# Testpoints.net
KiCad netlist of a schematic drawn in Altium Designer
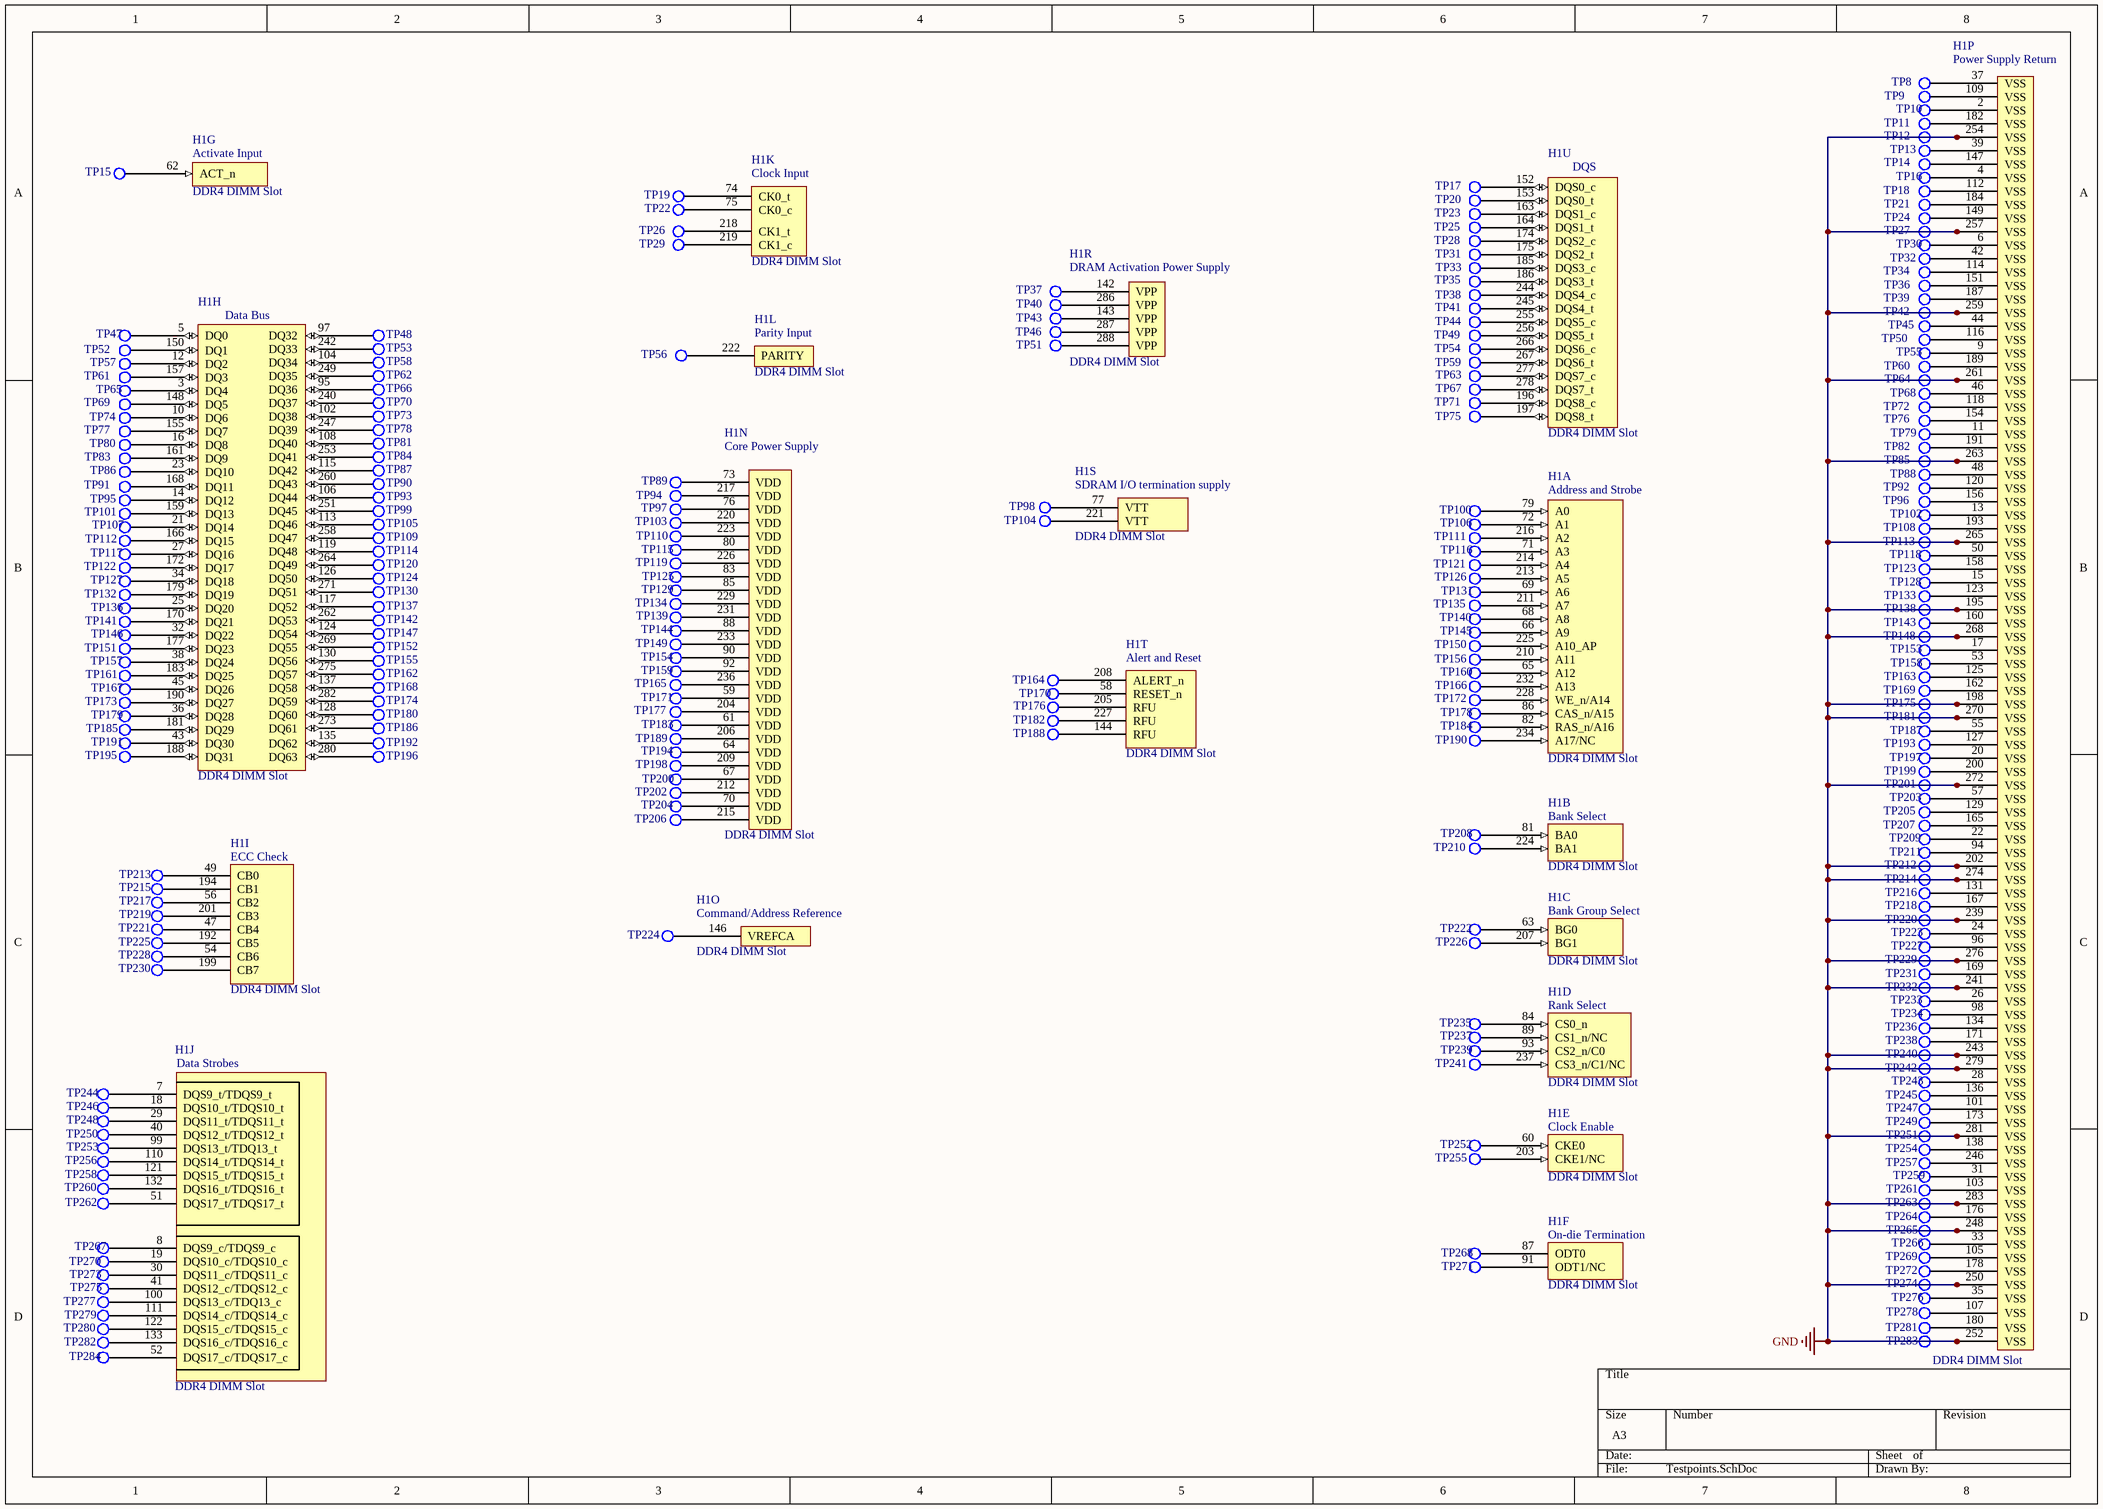
[diagram p0: Testpoints.SchDoc]

(export (version "E")
  (design (tool "Eeschema 10.0.6"))
  (components
    (comp (ref "H1")
      (value "DDR4 DIMM Slot")
      (footprint "DDR4 DIMM")
      (libsource (lib "RouterIntLib") (part "DDR4 DIMM Slot"))
    )
    (comp (ref "TP8")
      (value "Test Point")
      (footprint "Test Point")
      (libsource (lib "RouterIntLib") (part "Test Point"))
    )
    (comp (ref "TP9")
      (value "Test Point")
      (footprint "Test Point")
      (libsource (lib "RouterIntLib") (part "Test Point"))
    )
    (comp (ref "TP10")
      (value "Test Point")
      (footprint "Test Point")
      (libsource (lib "RouterIntLib") (part "Test Point"))
    )
    (comp (ref "TP11")
      (value "Test Point")
      (footprint "Test Point")
      (libsource (lib "RouterIntLib") (part "Test Point"))
    )
    (comp (ref "TP12")
      (value "Test Point")
      (footprint "Test Point")
      (libsource (lib "RouterIntLib") (part "Test Point"))
    )
    (comp (ref "TP13")
      (value "Test Point")
      (footprint "Test Point")
      (libsource (lib "RouterIntLib") (part "Test Point"))
    )
    (comp (ref "TP14")
      (value "Test Point")
      (footprint "Test Point")
      (libsource (lib "RouterIntLib") (part "Test Point"))
    )
    (comp (ref "TP15")
      (value "Test Point")
      (footprint "Test Point")
      (libsource (lib "RouterIntLib") (part "Test Point"))
    )
    (comp (ref "TP16")
      (value "Test Point")
      (footprint "Test Point")
      (libsource (lib "RouterIntLib") (part "Test Point"))
    )
    (comp (ref "TP17")
      (value "Test Point")
      (footprint "Test Point")
      (libsource (lib "RouterIntLib") (part "Test Point"))
    )
    (comp (ref "TP18")
      (value "Test Point")
      (footprint "Test Point")
      (libsource (lib "RouterIntLib") (part "Test Point"))
    )
    (comp (ref "TP19")
      (value "Test Point")
      (footprint "Test Point")
      (libsource (lib "RouterIntLib") (part "Test Point"))
    )
    (comp (ref "TP20")
      (value "Test Point")
      (footprint "Test Point")
      (libsource (lib "RouterIntLib") (part "Test Point"))
    )
    (comp (ref "TP21")
      (value "Test Point")
      (footprint "Test Point")
      (libsource (lib "RouterIntLib") (part "Test Point"))
    )
    (comp (ref "TP22")
      (value "Test Point")
      (footprint "Test Point")
      (libsource (lib "RouterIntLib") (part "Test Point"))
    )
    (comp (ref "TP23")
      (value "Test Point")
      (footprint "Test Point")
      (libsource (lib "RouterIntLib") (part "Test Point"))
    )
    (comp (ref "TP24")
      (value "Test Point")
      (footprint "Test Point")
      (libsource (lib "RouterIntLib") (part "Test Point"))
    )
    (comp (ref "TP25")
      (value "Test Point")
      (footprint "Test Point")
      (libsource (lib "RouterIntLib") (part "Test Point"))
    )
    (comp (ref "TP26")
      (value "Test Point")
      (footprint "Test Point")
      (libsource (lib "RouterIntLib") (part "Test Point"))
    )
    (comp (ref "TP27")
      (value "Test Point")
      (footprint "Test Point")
      (libsource (lib "RouterIntLib") (part "Test Point"))
    )
    (comp (ref "TP28")
      (value "Test Point")
      (footprint "Test Point")
      (libsource (lib "RouterIntLib") (part "Test Point"))
    )
    (comp (ref "TP29")
      (value "Test Point")
      (footprint "Test Point")
      (libsource (lib "RouterIntLib") (part "Test Point"))
    )
    (comp (ref "TP30")
      (value "Test Point")
      (footprint "Test Point")
      (libsource (lib "RouterIntLib") (part "Test Point"))
    )
    (comp (ref "TP31")
      (value "Test Point")
      (footprint "Test Point")
      (libsource (lib "RouterIntLib") (part "Test Point"))
    )
    (comp (ref "TP32")
      (value "Test Point")
      (footprint "Test Point")
      (libsource (lib "RouterIntLib") (part "Test Point"))
    )
    (comp (ref "TP33")
      (value "Test Point")
      (footprint "Test Point")
      (libsource (lib "RouterIntLib") (part "Test Point"))
    )
    (comp (ref "TP34")
      (value "Test Point")
      (footprint "Test Point")
      (libsource (lib "RouterIntLib") (part "Test Point"))
    )
    (comp (ref "TP35")
      (value "Test Point")
      (footprint "Test Point")
      (libsource (lib "RouterIntLib") (part "Test Point"))
    )
    (comp (ref "TP36")
      (value "Test Point")
      (footprint "Test Point")
      (libsource (lib "RouterIntLib") (part "Test Point"))
    )
    (comp (ref "TP37")
      (value "Test Point")
      (footprint "Test Point")
      (libsource (lib "RouterIntLib") (part "Test Point"))
    )
    (comp (ref "TP38")
      (value "Test Point")
      (footprint "Test Point")
      (libsource (lib "RouterIntLib") (part "Test Point"))
    )
    (comp (ref "TP39")
      (value "Test Point")
      (footprint "Test Point")
      (libsource (lib "RouterIntLib") (part "Test Point"))
    )
    (comp (ref "TP40")
      (value "Test Point")
      (footprint "Test Point")
      (libsource (lib "RouterIntLib") (part "Test Point"))
    )
    (comp (ref "TP41")
      (value "Test Point")
      (footprint "Test Point")
      (libsource (lib "RouterIntLib") (part "Test Point"))
    )
    (comp (ref "TP42")
      (value "Test Point")
      (footprint "Test Point")
      (libsource (lib "RouterIntLib") (part "Test Point"))
    )
    (comp (ref "TP43")
      (value "Test Point")
      (footprint "Test Point")
      (libsource (lib "RouterIntLib") (part "Test Point"))
    )
    (comp (ref "TP44")
      (value "Test Point")
      (footprint "Test Point")
      (libsource (lib "RouterIntLib") (part "Test Point"))
    )
    (comp (ref "TP45")
      (value "Test Point")
      (footprint "Test Point")
      (libsource (lib "RouterIntLib") (part "Test Point"))
    )
    (comp (ref "TP46")
      (value "Test Point")
      (footprint "Test Point")
      (libsource (lib "RouterIntLib") (part "Test Point"))
    )
    (comp (ref "TP47")
      (value "Test Point")
      (footprint "Test Point")
      (libsource (lib "RouterIntLib") (part "Test Point"))
    )
    (comp (ref "TP48")
      (value "Test Point")
      (footprint "Test Point")
      (libsource (lib "RouterIntLib") (part "Test Point"))
    )
    (comp (ref "TP49")
      (value "Test Point")
      (footprint "Test Point")
      (libsource (lib "RouterIntLib") (part "Test Point"))
    )
    (comp (ref "TP50")
      (value "Test Point")
      (footprint "Test Point")
      (libsource (lib "RouterIntLib") (part "Test Point"))
    )
    (comp (ref "TP51")
      (value "Test Point")
      (footprint "Test Point")
      (libsource (lib "RouterIntLib") (part "Test Point"))
    )
    (comp (ref "TP52")
      (value "Test Point")
      (footprint "Test Point")
      (libsource (lib "RouterIntLib") (part "Test Point"))
    )
    (comp (ref "TP53")
      (value "Test Point")
      (footprint "Test Point")
      (libsource (lib "RouterIntLib") (part "Test Point"))
    )
    (comp (ref "TP54")
      (value "Test Point")
      (footprint "Test Point")
      (libsource (lib "RouterIntLib") (part "Test Point"))
    )
    (comp (ref "TP55")
      (value "Test Point")
      (footprint "Test Point")
      (libsource (lib "RouterIntLib") (part "Test Point"))
    )
    (comp (ref "TP56")
      (value "Test Point")
      (footprint "Test Point")
      (libsource (lib "RouterIntLib") (part "Test Point"))
    )
    (comp (ref "TP57")
      (value "Test Point")
      (footprint "Test Point")
      (libsource (lib "RouterIntLib") (part "Test Point"))
    )
    (comp (ref "TP58")
      (value "Test Point")
      (footprint "Test Point")
      (libsource (lib "RouterIntLib") (part "Test Point"))
    )
    (comp (ref "TP59")
      (value "Test Point")
      (footprint "Test Point")
      (libsource (lib "RouterIntLib") (part "Test Point"))
    )
    (comp (ref "TP60")
      (value "Test Point")
      (footprint "Test Point")
      (libsource (lib "RouterIntLib") (part "Test Point"))
    )
    (comp (ref "TP61")
      (value "Test Point")
      (footprint "Test Point")
      (libsource (lib "RouterIntLib") (part "Test Point"))
    )
    (comp (ref "TP62")
      (value "Test Point")
      (footprint "Test Point")
      (libsource (lib "RouterIntLib") (part "Test Point"))
    )
    (comp (ref "TP63")
      (value "Test Point")
      (footprint "Test Point")
      (libsource (lib "RouterIntLib") (part "Test Point"))
    )
    (comp (ref "TP64")
      (value "Test Point")
      (footprint "Test Point")
      (libsource (lib "RouterIntLib") (part "Test Point"))
    )
    (comp (ref "TP65")
      (value "Test Point")
      (footprint "Test Point")
      (libsource (lib "RouterIntLib") (part "Test Point"))
    )
    (comp (ref "TP66")
      (value "Test Point")
      (footprint "Test Point")
      (libsource (lib "RouterIntLib") (part "Test Point"))
    )
    (comp (ref "TP67")
      (value "Test Point")
      (footprint "Test Point")
      (libsource (lib "RouterIntLib") (part "Test Point"))
    )
    (comp (ref "TP68")
      (value "Test Point")
      (footprint "Test Point")
      (libsource (lib "RouterIntLib") (part "Test Point"))
    )
    (comp (ref "TP69")
      (value "Test Point")
      (footprint "Test Point")
      (libsource (lib "RouterIntLib") (part "Test Point"))
    )
    (comp (ref "TP70")
      (value "Test Point")
      (footprint "Test Point")
      (libsource (lib "RouterIntLib") (part "Test Point"))
    )
    (comp (ref "TP71")
      (value "Test Point")
      (footprint "Test Point")
      (libsource (lib "RouterIntLib") (part "Test Point"))
    )
    (comp (ref "TP72")
      (value "Test Point")
      (footprint "Test Point")
      (libsource (lib "RouterIntLib") (part "Test Point"))
    )
    (comp (ref "TP73")
      (value "Test Point")
      (footprint "Test Point")
      (libsource (lib "RouterIntLib") (part "Test Point"))
    )
    (comp (ref "TP74")
      (value "Test Point")
      (footprint "Test Point")
      (libsource (lib "RouterIntLib") (part "Test Point"))
    )
    (comp (ref "TP75")
      (value "Test Point")
      (footprint "Test Point")
      (libsource (lib "RouterIntLib") (part "Test Point"))
    )
    (comp (ref "TP76")
      (value "Test Point")
      (footprint "Test Point")
      (libsource (lib "RouterIntLib") (part "Test Point"))
    )
    (comp (ref "TP77")
      (value "Test Point")
      (footprint "Test Point")
      (libsource (lib "RouterIntLib") (part "Test Point"))
    )
    (comp (ref "TP78")
      (value "Test Point")
      (footprint "Test Point")
      (libsource (lib "RouterIntLib") (part "Test Point"))
    )
    (comp (ref "TP79")
      (value "Test Point")
      (footprint "Test Point")
      (libsource (lib "RouterIntLib") (part "Test Point"))
    )
    (comp (ref "TP80")
      (value "Test Point")
      (footprint "Test Point")
      (libsource (lib "RouterIntLib") (part "Test Point"))
    )
    (comp (ref "TP81")
      (value "Test Point")
      (footprint "Test Point")
      (libsource (lib "RouterIntLib") (part "Test Point"))
    )
    (comp (ref "TP82")
      (value "Test Point")
      (footprint "Test Point")
      (libsource (lib "RouterIntLib") (part "Test Point"))
    )
    (comp (ref "TP83")
      (value "Test Point")
      (footprint "Test Point")
      (libsource (lib "RouterIntLib") (part "Test Point"))
    )
    (comp (ref "TP84")
      (value "Test Point")
      (footprint "Test Point")
      (libsource (lib "RouterIntLib") (part "Test Point"))
    )
    (comp (ref "TP85")
      (value "Test Point")
      (footprint "Test Point")
      (libsource (lib "RouterIntLib") (part "Test Point"))
    )
    (comp (ref "TP86")
      (value "Test Point")
      (footprint "Test Point")
      (libsource (lib "RouterIntLib") (part "Test Point"))
    )
    (comp (ref "TP87")
      (value "Test Point")
      (footprint "Test Point")
      (libsource (lib "RouterIntLib") (part "Test Point"))
    )
    (comp (ref "TP88")
      (value "Test Point")
      (footprint "Test Point")
      (libsource (lib "RouterIntLib") (part "Test Point"))
    )
    (comp (ref "TP89")
      (value "Test Point")
      (footprint "Test Point")
      (libsource (lib "RouterIntLib") (part "Test Point"))
    )
    (comp (ref "TP90")
      (value "Test Point")
      (footprint "Test Point")
      (libsource (lib "RouterIntLib") (part "Test Point"))
    )
    (comp (ref "TP91")
      (value "Test Point")
      (footprint "Test Point")
      (libsource (lib "RouterIntLib") (part "Test Point"))
    )
    (comp (ref "TP92")
      (value "Test Point")
      (footprint "Test Point")
      (libsource (lib "RouterIntLib") (part "Test Point"))
    )
    (comp (ref "TP93")
      (value "Test Point")
      (footprint "Test Point")
      (libsource (lib "RouterIntLib") (part "Test Point"))
    )
    (comp (ref "TP94")
      (value "Test Point")
      (footprint "Test Point")
      (libsource (lib "RouterIntLib") (part "Test Point"))
    )
    (comp (ref "TP95")
      (value "Test Point")
      (footprint "Test Point")
      (libsource (lib "RouterIntLib") (part "Test Point"))
    )
    (comp (ref "TP96")
      (value "Test Point")
      (footprint "Test Point")
      (libsource (lib "RouterIntLib") (part "Test Point"))
    )
    (comp (ref "TP97")
      (value "Test Point")
      (footprint "Test Point")
      (libsource (lib "RouterIntLib") (part "Test Point"))
    )
    (comp (ref "TP98")
      (value "Test Point")
      (footprint "Test Point")
      (libsource (lib "RouterIntLib") (part "Test Point"))
    )
    (comp (ref "TP99")
      (value "Test Point")
      (footprint "Test Point")
      (libsource (lib "RouterIntLib") (part "Test Point"))
    )
    (comp (ref "TP100")
      (value "Test Point")
      (footprint "Test Point")
      (libsource (lib "RouterIntLib") (part "Test Point"))
    )
    (comp (ref "TP101")
      (value "Test Point")
      (footprint "Test Point")
      (libsource (lib "RouterIntLib") (part "Test Point"))
    )
    (comp (ref "TP102")
      (value "Test Point")
      (footprint "Test Point")
      (libsource (lib "RouterIntLib") (part "Test Point"))
    )
    (comp (ref "TP103")
      (value "Test Point")
      (footprint "Test Point")
      (libsource (lib "RouterIntLib") (part "Test Point"))
    )
    (comp (ref "TP104")
      (value "Test Point")
      (footprint "Test Point")
      (libsource (lib "RouterIntLib") (part "Test Point"))
    )
    (comp (ref "TP105")
      (value "Test Point")
      (footprint "Test Point")
      (libsource (lib "RouterIntLib") (part "Test Point"))
    )
    (comp (ref "TP106")
      (value "Test Point")
      (footprint "Test Point")
      (libsource (lib "RouterIntLib") (part "Test Point"))
    )
    (comp (ref "TP107")
      (value "Test Point")
      (footprint "Test Point")
      (libsource (lib "RouterIntLib") (part "Test Point"))
    )
    (comp (ref "TP108")
      (value "Test Point")
      (footprint "Test Point")
      (libsource (lib "RouterIntLib") (part "Test Point"))
    )
    (comp (ref "TP109")
      (value "Test Point")
      (footprint "Test Point")
      (libsource (lib "RouterIntLib") (part "Test Point"))
    )
    (comp (ref "TP110")
      (value "Test Point")
      (footprint "Test Point")
      (libsource (lib "RouterIntLib") (part "Test Point"))
    )
    (comp (ref "TP111")
      (value "Test Point")
      (footprint "Test Point")
      (libsource (lib "RouterIntLib") (part "Test Point"))
    )
    (comp (ref "TP112")
      (value "Test Point")
      (footprint "Test Point")
      (libsource (lib "RouterIntLib") (part "Test Point"))
    )
    (comp (ref "TP113")
      (value "Test Point")
      (footprint "Test Point")
      (libsource (lib "RouterIntLib") (part "Test Point"))
    )
    (comp (ref "TP114")
      (value "Test Point")
      (footprint "Test Point")
      (libsource (lib "RouterIntLib") (part "Test Point"))
    )
    (comp (ref "TP115")
      (value "Test Point")
      (footprint "Test Point")
      (libsource (lib "RouterIntLib") (part "Test Point"))
    )
    (comp (ref "TP116")
      (value "Test Point")
      (footprint "Test Point")
      (libsource (lib "RouterIntLib") (part "Test Point"))
    )
    (comp (ref "TP117")
      (value "Test Point")
      (footprint "Test Point")
      (libsource (lib "RouterIntLib") (part "Test Point"))
    )
    (comp (ref "TP118")
      (value "Test Point")
      (footprint "Test Point")
      (libsource (lib "RouterIntLib") (part "Test Point"))
    )
    (comp (ref "TP119")
      (value "Test Point")
      (footprint "Test Point")
      (libsource (lib "RouterIntLib") (part "Test Point"))
    )
    (comp (ref "TP120")
      (value "Test Point")
      (footprint "Test Point")
      (libsource (lib "RouterIntLib") (part "Test Point"))
    )
    (comp (ref "TP121")
      (value "Test Point")
      (footprint "Test Point")
      (libsource (lib "RouterIntLib") (part "Test Point"))
    )
    (comp (ref "TP122")
      (value "Test Point")
      (footprint "Test Point")
      (libsource (lib "RouterIntLib") (part "Test Point"))
    )
    (comp (ref "TP123")
      (value "Test Point")
      (footprint "Test Point")
      (libsource (lib "RouterIntLib") (part "Test Point"))
    )
    (comp (ref "TP124")
      (value "Test Point")
      (footprint "Test Point")
      (libsource (lib "RouterIntLib") (part "Test Point"))
    )
    (comp (ref "TP125")
      (value "Test Point")
      (footprint "Test Point")
      (libsource (lib "RouterIntLib") (part "Test Point"))
    )
    (comp (ref "TP126")
      (value "Test Point")
      (footprint "Test Point")
      (libsource (lib "RouterIntLib") (part "Test Point"))
    )
    (comp (ref "TP127")
      (value "Test Point")
      (footprint "Test Point")
      (libsource (lib "RouterIntLib") (part "Test Point"))
    )
    (comp (ref "TP128")
      (value "Test Point")
      (footprint "Test Point")
      (libsource (lib "RouterIntLib") (part "Test Point"))
    )
    (comp (ref "TP129")
      (value "Test Point")
      (footprint "Test Point")
      (libsource (lib "RouterIntLib") (part "Test Point"))
    )
    (comp (ref "TP130")
      (value "Test Point")
      (footprint "Test Point")
      (libsource (lib "RouterIntLib") (part "Test Point"))
    )
    (comp (ref "TP131")
      (value "Test Point")
      (footprint "Test Point")
      (libsource (lib "RouterIntLib") (part "Test Point"))
    )
    (comp (ref "TP132")
      (value "Test Point")
      (footprint "Test Point")
      (libsource (lib "RouterIntLib") (part "Test Point"))
    )
    (comp (ref "TP133")
      (value "Test Point")
      (footprint "Test Point")
      (libsource (lib "RouterIntLib") (part "Test Point"))
    )
    (comp (ref "TP134")
      (value "Test Point")
      (footprint "Test Point")
      (libsource (lib "RouterIntLib") (part "Test Point"))
    )
    (comp (ref "TP135")
      (value "Test Point")
      (footprint "Test Point")
      (libsource (lib "RouterIntLib") (part "Test Point"))
    )
    (comp (ref "TP136")
      (value "Test Point")
      (footprint "Test Point")
      (libsource (lib "RouterIntLib") (part "Test Point"))
    )
    (comp (ref "TP137")
      (value "Test Point")
      (footprint "Test Point")
      (libsource (lib "RouterIntLib") (part "Test Point"))
    )
    (comp (ref "TP138")
      (value "Test Point")
      (footprint "Test Point")
      (libsource (lib "RouterIntLib") (part "Test Point"))
    )
    (comp (ref "TP139")
      (value "Test Point")
      (footprint "Test Point")
      (libsource (lib "RouterIntLib") (part "Test Point"))
    )
    (comp (ref "TP140")
      (value "Test Point")
      (footprint "Test Point")
      (libsource (lib "RouterIntLib") (part "Test Point"))
    )
    (comp (ref "TP141")
      (value "Test Point")
      (footprint "Test Point")
      (libsource (lib "RouterIntLib") (part "Test Point"))
    )
    (comp (ref "TP142")
      (value "Test Point")
      (footprint "Test Point")
      (libsource (lib "RouterIntLib") (part "Test Point"))
    )
    (comp (ref "TP143")
      (value "Test Point")
      (footprint "Test Point")
      (libsource (lib "RouterIntLib") (part "Test Point"))
    )
    (comp (ref "TP144")
      (value "Test Point")
      (footprint "Test Point")
      (libsource (lib "RouterIntLib") (part "Test Point"))
    )
    (comp (ref "TP145")
      (value "Test Point")
      (footprint "Test Point")
      (libsource (lib "RouterIntLib") (part "Test Point"))
    )
    (comp (ref "TP146")
      (value "Test Point")
      (footprint "Test Point")
      (libsource (lib "RouterIntLib") (part "Test Point"))
    )
    (comp (ref "TP147")
      (value "Test Point")
      (footprint "Test Point")
      (libsource (lib "RouterIntLib") (part "Test Point"))
    )
    (comp (ref "TP148")
      (value "Test Point")
      (footprint "Test Point")
      (libsource (lib "RouterIntLib") (part "Test Point"))
    )
    (comp (ref "TP149")
      (value "Test Point")
      (footprint "Test Point")
      (libsource (lib "RouterIntLib") (part "Test Point"))
    )
    (comp (ref "TP150")
      (value "Test Point")
      (footprint "Test Point")
      (libsource (lib "RouterIntLib") (part "Test Point"))
    )
    (comp (ref "TP151")
      (value "Test Point")
      (footprint "Test Point")
      (libsource (lib "RouterIntLib") (part "Test Point"))
    )
    (comp (ref "TP152")
      (value "Test Point")
      (footprint "Test Point")
      (libsource (lib "RouterIntLib") (part "Test Point"))
    )
    (comp (ref "TP153")
      (value "Test Point")
      (footprint "Test Point")
      (libsource (lib "RouterIntLib") (part "Test Point"))
    )
    (comp (ref "TP154")
      (value "Test Point")
      (footprint "Test Point")
      (libsource (lib "RouterIntLib") (part "Test Point"))
    )
    (comp (ref "TP155")
      (value "Test Point")
      (footprint "Test Point")
      (libsource (lib "RouterIntLib") (part "Test Point"))
    )
    (comp (ref "TP156")
      (value "Test Point")
      (footprint "Test Point")
      (libsource (lib "RouterIntLib") (part "Test Point"))
    )
    (comp (ref "TP157")
      (value "Test Point")
      (footprint "Test Point")
      (libsource (lib "RouterIntLib") (part "Test Point"))
    )
    (comp (ref "TP158")
      (value "Test Point")
      (footprint "Test Point")
      (libsource (lib "RouterIntLib") (part "Test Point"))
    )
    (comp (ref "TP159")
      (value "Test Point")
      (footprint "Test Point")
      (libsource (lib "RouterIntLib") (part "Test Point"))
    )
    (comp (ref "TP160")
      (value "Test Point")
      (footprint "Test Point")
      (libsource (lib "RouterIntLib") (part "Test Point"))
    )
    (comp (ref "TP161")
      (value "Test Point")
      (footprint "Test Point")
      (libsource (lib "RouterIntLib") (part "Test Point"))
    )
    (comp (ref "TP162")
      (value "Test Point")
      (footprint "Test Point")
      (libsource (lib "RouterIntLib") (part "Test Point"))
    )
    (comp (ref "TP163")
      (value "Test Point")
      (footprint "Test Point")
      (libsource (lib "RouterIntLib") (part "Test Point"))
    )
    (comp (ref "TP164")
      (value "Test Point")
      (footprint "Test Point")
      (libsource (lib "RouterIntLib") (part "Test Point"))
    )
    (comp (ref "TP165")
      (value "Test Point")
      (footprint "Test Point")
      (libsource (lib "RouterIntLib") (part "Test Point"))
    )
    (comp (ref "TP166")
      (value "Test Point")
      (footprint "Test Point")
      (libsource (lib "RouterIntLib") (part "Test Point"))
    )
    (comp (ref "TP167")
      (value "Test Point")
      (footprint "Test Point")
      (libsource (lib "RouterIntLib") (part "Test Point"))
    )
    (comp (ref "TP168")
      (value "Test Point")
      (footprint "Test Point")
      (libsource (lib "RouterIntLib") (part "Test Point"))
    )
    (comp (ref "TP169")
      (value "Test Point")
      (footprint "Test Point")
      (libsource (lib "RouterIntLib") (part "Test Point"))
    )
    (comp (ref "TP170")
      (value "Test Point")
      (footprint "Test Point")
      (libsource (lib "RouterIntLib") (part "Test Point"))
    )
    (comp (ref "TP171")
      (value "Test Point")
      (footprint "Test Point")
      (libsource (lib "RouterIntLib") (part "Test Point"))
    )
    (comp (ref "TP172")
      (value "Test Point")
      (footprint "Test Point")
      (libsource (lib "RouterIntLib") (part "Test Point"))
    )
    (comp (ref "TP173")
      (value "Test Point")
      (footprint "Test Point")
      (libsource (lib "RouterIntLib") (part "Test Point"))
    )
    (comp (ref "TP174")
      (value "Test Point")
      (footprint "Test Point")
      (libsource (lib "RouterIntLib") (part "Test Point"))
    )
    (comp (ref "TP175")
      (value "Test Point")
      (footprint "Test Point")
      (libsource (lib "RouterIntLib") (part "Test Point"))
    )
    (comp (ref "TP176")
      (value "Test Point")
      (footprint "Test Point")
      (libsource (lib "RouterIntLib") (part "Test Point"))
    )
    (comp (ref "TP177")
      (value "Test Point")
      (footprint "Test Point")
      (libsource (lib "RouterIntLib") (part "Test Point"))
    )
    (comp (ref "TP178")
      (value "Test Point")
      (footprint "Test Point")
      (libsource (lib "RouterIntLib") (part "Test Point"))
    )
    (comp (ref "TP179")
      (value "Test Point")
      (footprint "Test Point")
      (libsource (lib "RouterIntLib") (part "Test Point"))
    )
    (comp (ref "TP180")
      (value "Test Point")
      (footprint "Test Point")
      (libsource (lib "RouterIntLib") (part "Test Point"))
    )
    (comp (ref "TP181")
      (value "Test Point")
      (footprint "Test Point")
      (libsource (lib "RouterIntLib") (part "Test Point"))
    )
    (comp (ref "TP182")
      (value "Test Point")
      (footprint "Test Point")
      (libsource (lib "RouterIntLib") (part "Test Point"))
    )
    (comp (ref "TP183")
      (value "Test Point")
      (footprint "Test Point")
      (libsource (lib "RouterIntLib") (part "Test Point"))
    )
    (comp (ref "TP184")
      (value "Test Point")
      (footprint "Test Point")
      (libsource (lib "RouterIntLib") (part "Test Point"))
    )
    (comp (ref "TP185")
      (value "Test Point")
      (footprint "Test Point")
      (libsource (lib "RouterIntLib") (part "Test Point"))
    )
    (comp (ref "TP186")
      (value "Test Point")
      (footprint "Test Point")
      (libsource (lib "RouterIntLib") (part "Test Point"))
    )
    (comp (ref "TP187")
      (value "Test Point")
      (footprint "Test Point")
      (libsource (lib "RouterIntLib") (part "Test Point"))
    )
    (comp (ref "TP188")
      (value "Test Point")
      (footprint "Test Point")
      (libsource (lib "RouterIntLib") (part "Test Point"))
    )
    (comp (ref "TP189")
      (value "Test Point")
      (footprint "Test Point")
      (libsource (lib "RouterIntLib") (part "Test Point"))
    )
    (comp (ref "TP190")
      (value "Test Point")
      (footprint "Test Point")
      (libsource (lib "RouterIntLib") (part "Test Point"))
    )
    (comp (ref "TP191")
      (value "Test Point")
      (footprint "Test Point")
      (libsource (lib "RouterIntLib") (part "Test Point"))
    )
    (comp (ref "TP192")
      (value "Test Point")
      (footprint "Test Point")
      (libsource (lib "RouterIntLib") (part "Test Point"))
    )
    (comp (ref "TP193")
      (value "Test Point")
      (footprint "Test Point")
      (libsource (lib "RouterIntLib") (part "Test Point"))
    )
    (comp (ref "TP194")
      (value "Test Point")
      (footprint "Test Point")
      (libsource (lib "RouterIntLib") (part "Test Point"))
    )
    (comp (ref "TP195")
      (value "Test Point")
      (footprint "Test Point")
      (libsource (lib "RouterIntLib") (part "Test Point"))
    )
    (comp (ref "TP196")
      (value "Test Point")
      (footprint "Test Point")
      (libsource (lib "RouterIntLib") (part "Test Point"))
    )
    (comp (ref "TP197")
      (value "Test Point")
      (footprint "Test Point")
      (libsource (lib "RouterIntLib") (part "Test Point"))
    )
    (comp (ref "TP198")
      (value "Test Point")
      (footprint "Test Point")
      (libsource (lib "RouterIntLib") (part "Test Point"))
    )
    (comp (ref "TP199")
      (value "Test Point")
      (footprint "Test Point")
      (libsource (lib "RouterIntLib") (part "Test Point"))
    )
    (comp (ref "TP200")
      (value "Test Point")
      (footprint "Test Point")
      (libsource (lib "RouterIntLib") (part "Test Point"))
    )
    (comp (ref "TP201")
      (value "Test Point")
      (footprint "Test Point")
      (libsource (lib "RouterIntLib") (part "Test Point"))
    )
    (comp (ref "TP202")
      (value "Test Point")
      (footprint "Test Point")
      (libsource (lib "RouterIntLib") (part "Test Point"))
    )
    (comp (ref "TP203")
      (value "Test Point")
      (footprint "Test Point")
      (libsource (lib "RouterIntLib") (part "Test Point"))
    )
    (comp (ref "TP204")
      (value "Test Point")
      (footprint "Test Point")
      (libsource (lib "RouterIntLib") (part "Test Point"))
    )
    (comp (ref "TP205")
      (value "Test Point")
      (footprint "Test Point")
      (libsource (lib "RouterIntLib") (part "Test Point"))
    )
    (comp (ref "TP206")
      (value "Test Point")
      (footprint "Test Point")
      (libsource (lib "RouterIntLib") (part "Test Point"))
    )
    (comp (ref "TP207")
      (value "Test Point")
      (footprint "Test Point")
      (libsource (lib "RouterIntLib") (part "Test Point"))
    )
    (comp (ref "TP208")
      (value "Test Point")
      (footprint "Test Point")
      (libsource (lib "RouterIntLib") (part "Test Point"))
    )
    (comp (ref "TP209")
      (value "Test Point")
      (footprint "Test Point")
      (libsource (lib "RouterIntLib") (part "Test Point"))
    )
    (comp (ref "TP210")
      (value "Test Point")
      (footprint "Test Point")
      (libsource (lib "RouterIntLib") (part "Test Point"))
    )
    (comp (ref "TP211")
      (value "Test Point")
      (footprint "Test Point")
      (libsource (lib "RouterIntLib") (part "Test Point"))
    )
    (comp (ref "TP212")
      (value "Test Point")
      (footprint "Test Point")
      (libsource (lib "RouterIntLib") (part "Test Point"))
    )
    (comp (ref "TP213")
      (value "Test Point")
      (footprint "Test Point")
      (libsource (lib "RouterIntLib") (part "Test Point"))
    )
    (comp (ref "TP214")
      (value "Test Point")
      (footprint "Test Point")
      (libsource (lib "RouterIntLib") (part "Test Point"))
    )
    (comp (ref "TP215")
      (value "Test Point")
      (footprint "Test Point")
      (libsource (lib "RouterIntLib") (part "Test Point"))
    )
    (comp (ref "TP216")
      (value "Test Point")
      (footprint "Test Point")
      (libsource (lib "RouterIntLib") (part "Test Point"))
    )
    (comp (ref "TP217")
      (value "Test Point")
      (footprint "Test Point")
      (libsource (lib "RouterIntLib") (part "Test Point"))
    )
    (comp (ref "TP218")
      (value "Test Point")
      (footprint "Test Point")
      (libsource (lib "RouterIntLib") (part "Test Point"))
    )
    (comp (ref "TP219")
      (value "Test Point")
      (footprint "Test Point")
      (libsource (lib "RouterIntLib") (part "Test Point"))
    )
    (comp (ref "TP220")
      (value "Test Point")
      (footprint "Test Point")
      (libsource (lib "RouterIntLib") (part "Test Point"))
    )
    (comp (ref "TP221")
      (value "Test Point")
      (footprint "Test Point")
      (libsource (lib "RouterIntLib") (part "Test Point"))
    )
    (comp (ref "TP222")
      (value "Test Point")
      (footprint "Test Point")
      (libsource (lib "RouterIntLib") (part "Test Point"))
    )
    (comp (ref "TP223")
      (value "Test Point")
      (footprint "Test Point")
      (libsource (lib "RouterIntLib") (part "Test Point"))
    )
    (comp (ref "TP224")
      (value "Test Point")
      (footprint "Test Point")
      (libsource (lib "RouterIntLib") (part "Test Point"))
    )
    (comp (ref "TP225")
      (value "Test Point")
      (footprint "Test Point")
      (libsource (lib "RouterIntLib") (part "Test Point"))
    )
    (comp (ref "TP226")
      (value "Test Point")
      (footprint "Test Point")
      (libsource (lib "RouterIntLib") (part "Test Point"))
    )
    (comp (ref "TP227")
      (value "Test Point")
      (footprint "Test Point")
      (libsource (lib "RouterIntLib") (part "Test Point"))
    )
    (comp (ref "TP228")
      (value "Test Point")
      (footprint "Test Point")
      (libsource (lib "RouterIntLib") (part "Test Point"))
    )
    (comp (ref "TP229")
      (value "Test Point")
      (footprint "Test Point")
      (libsource (lib "RouterIntLib") (part "Test Point"))
    )
    (comp (ref "TP230")
      (value "Test Point")
      (footprint "Test Point")
      (libsource (lib "RouterIntLib") (part "Test Point"))
    )
    (comp (ref "TP231")
      (value "Test Point")
      (footprint "Test Point")
      (libsource (lib "RouterIntLib") (part "Test Point"))
    )
    (comp (ref "TP232")
      (value "Test Point")
      (footprint "Test Point")
      (libsource (lib "RouterIntLib") (part "Test Point"))
    )
    (comp (ref "TP233")
      (value "Test Point")
      (footprint "Test Point")
      (libsource (lib "RouterIntLib") (part "Test Point"))
    )
    (comp (ref "TP234")
      (value "Test Point")
      (footprint "Test Point")
      (libsource (lib "RouterIntLib") (part "Test Point"))
    )
    (comp (ref "TP235")
      (value "Test Point")
      (footprint "Test Point")
      (libsource (lib "RouterIntLib") (part "Test Point"))
    )
    (comp (ref "TP236")
      (value "Test Point")
      (footprint "Test Point")
      (libsource (lib "RouterIntLib") (part "Test Point"))
    )
    (comp (ref "TP237")
      (value "Test Point")
      (footprint "Test Point")
      (libsource (lib "RouterIntLib") (part "Test Point"))
    )
    (comp (ref "TP238")
      (value "Test Point")
      (footprint "Test Point")
      (libsource (lib "RouterIntLib") (part "Test Point"))
    )
    (comp (ref "TP239")
      (value "Test Point")
      (footprint "Test Point")
      (libsource (lib "RouterIntLib") (part "Test Point"))
    )
    (comp (ref "TP240")
      (value "Test Point")
      (footprint "Test Point")
      (libsource (lib "RouterIntLib") (part "Test Point"))
    )
    (comp (ref "TP241")
      (value "Test Point")
      (footprint "Test Point")
      (libsource (lib "RouterIntLib") (part "Test Point"))
    )
    (comp (ref "TP242")
      (value "Test Point")
      (footprint "Test Point")
      (libsource (lib "RouterIntLib") (part "Test Point"))
    )
    (comp (ref "TP243")
      (value "Test Point")
      (footprint "Test Point")
      (libsource (lib "RouterIntLib") (part "Test Point"))
    )
    (comp (ref "TP244")
      (value "Test Point")
      (footprint "Test Point")
      (libsource (lib "RouterIntLib") (part "Test Point"))
    )
    (comp (ref "TP245")
      (value "Test Point")
      (footprint "Test Point")
      (libsource (lib "RouterIntLib") (part "Test Point"))
    )
    (comp (ref "TP246")
      (value "Test Point")
      (footprint "Test Point")
      (libsource (lib "RouterIntLib") (part "Test Point"))
    )
    (comp (ref "TP247")
      (value "Test Point")
      (footprint "Test Point")
      (libsource (lib "RouterIntLib") (part "Test Point"))
    )
    (comp (ref "TP248")
      (value "Test Point")
      (footprint "Test Point")
      (libsource (lib "RouterIntLib") (part "Test Point"))
    )
    (comp (ref "TP249")
      (value "Test Point")
      (footprint "Test Point")
      (libsource (lib "RouterIntLib") (part "Test Point"))
    )
    (comp (ref "TP250")
      (value "Test Point")
      (footprint "Test Point")
      (libsource (lib "RouterIntLib") (part "Test Point"))
    )
    (comp (ref "TP251")
      (value "Test Point")
      (footprint "Test Point")
      (libsource (lib "RouterIntLib") (part "Test Point"))
    )
    (comp (ref "TP252")
      (value "Test Point")
      (footprint "Test Point")
      (libsource (lib "RouterIntLib") (part "Test Point"))
    )
    (comp (ref "TP253")
      (value "Test Point")
      (footprint "Test Point")
      (libsource (lib "RouterIntLib") (part "Test Point"))
    )
    (comp (ref "TP254")
      (value "Test Point")
      (footprint "Test Point")
      (libsource (lib "RouterIntLib") (part "Test Point"))
    )
    (comp (ref "TP255")
      (value "Test Point")
      (footprint "Test Point")
      (libsource (lib "RouterIntLib") (part "Test Point"))
    )
    (comp (ref "TP256")
      (value "Test Point")
      (footprint "Test Point")
      (libsource (lib "RouterIntLib") (part "Test Point"))
    )
    (comp (ref "TP257")
      (value "Test Point")
      (footprint "Test Point")
      (libsource (lib "RouterIntLib") (part "Test Point"))
    )
    (comp (ref "TP258")
      (value "Test Point")
      (footprint "Test Point")
      (libsource (lib "RouterIntLib") (part "Test Point"))
    )
    (comp (ref "TP259")
      (value "Test Point")
      (footprint "Test Point")
      (libsource (lib "RouterIntLib") (part "Test Point"))
    )
    (comp (ref "TP260")
      (value "Test Point")
      (footprint "Test Point")
      (libsource (lib "RouterIntLib") (part "Test Point"))
    )
    (comp (ref "TP261")
      (value "Test Point")
      (footprint "Test Point")
      (libsource (lib "RouterIntLib") (part "Test Point"))
    )
    (comp (ref "TP262")
      (value "Test Point")
      (footprint "Test Point")
      (libsource (lib "RouterIntLib") (part "Test Point"))
    )
    (comp (ref "TP263")
      (value "Test Point")
      (footprint "Test Point")
      (libsource (lib "RouterIntLib") (part "Test Point"))
    )
    (comp (ref "TP264")
      (value "Test Point")
      (footprint "Test Point")
      (libsource (lib "RouterIntLib") (part "Test Point"))
    )
    (comp (ref "TP265")
      (value "Test Point")
      (footprint "Test Point")
      (libsource (lib "RouterIntLib") (part "Test Point"))
    )
    (comp (ref "TP266")
      (value "Test Point")
      (footprint "Test Point")
      (libsource (lib "RouterIntLib") (part "Test Point"))
    )
    (comp (ref "TP267")
      (value "Test Point")
      (footprint "Test Point")
      (libsource (lib "RouterIntLib") (part "Test Point"))
    )
    (comp (ref "TP268")
      (value "Test Point")
      (footprint "Test Point")
      (libsource (lib "RouterIntLib") (part "Test Point"))
    )
    (comp (ref "TP269")
      (value "Test Point")
      (footprint "Test Point")
      (libsource (lib "RouterIntLib") (part "Test Point"))
    )
    (comp (ref "TP270")
      (value "Test Point")
      (footprint "Test Point")
      (libsource (lib "RouterIntLib") (part "Test Point"))
    )
    (comp (ref "TP271")
      (value "Test Point")
      (footprint "Test Point")
      (libsource (lib "RouterIntLib") (part "Test Point"))
    )
    (comp (ref "TP272")
      (value "Test Point")
      (footprint "Test Point")
      (libsource (lib "RouterIntLib") (part "Test Point"))
    )
    (comp (ref "TP273")
      (value "Test Point")
      (footprint "Test Point")
      (libsource (lib "RouterIntLib") (part "Test Point"))
    )
    (comp (ref "TP274")
      (value "Test Point")
      (footprint "Test Point")
      (libsource (lib "RouterIntLib") (part "Test Point"))
    )
    (comp (ref "TP275")
      (value "Test Point")
      (footprint "Test Point")
      (libsource (lib "RouterIntLib") (part "Test Point"))
    )
    (comp (ref "TP276")
      (value "Test Point")
      (footprint "Test Point")
      (libsource (lib "RouterIntLib") (part "Test Point"))
    )
    (comp (ref "TP277")
      (value "Test Point")
      (footprint "Test Point")
      (libsource (lib "RouterIntLib") (part "Test Point"))
    )
    (comp (ref "TP278")
      (value "Test Point")
      (footprint "Test Point")
      (libsource (lib "RouterIntLib") (part "Test Point"))
    )
    (comp (ref "TP279")
      (value "Test Point")
      (footprint "Test Point")
      (libsource (lib "RouterIntLib") (part "Test Point"))
    )
    (comp (ref "TP280")
      (value "Test Point")
      (footprint "Test Point")
      (libsource (lib "RouterIntLib") (part "Test Point"))
    )
    (comp (ref "TP281")
      (value "Test Point")
      (footprint "Test Point")
      (libsource (lib "RouterIntLib") (part "Test Point"))
    )
    (comp (ref "TP282")
      (value "Test Point")
      (footprint "Test Point")
      (libsource (lib "RouterIntLib") (part "Test Point"))
    )
    (comp (ref "TP283")
      (value "Test Point")
      (footprint "Test Point")
      (libsource (lib "RouterIntLib") (part "Test Point"))
    )
    (comp (ref "TP284")
      (value "Test Point")
      (footprint "Test Point")
      (libsource (lib "RouterIntLib") (part "Test Point"))
    )
  )
  (nets
    (net (code "1") (name "GND") (class "Default")
      (node (ref "H1") (pin "195") (pinfunction "VSS_195") (pintype "passive"))
      (node (ref "H1") (pin "198") (pinfunction "VSS_198") (pintype "passive"))
      (node (ref "H1") (pin "202") (pinfunction "VSS_202") (pintype "passive"))
      (node (ref "H1") (pin "239") (pinfunction "VSS_239") (pintype "passive"))
      (node (ref "H1") (pin "241") (pinfunction "VSS_241") (pintype "passive"))
      (node (ref "H1") (pin "243") (pinfunction "VSS_243") (pintype "passive"))
      (node (ref "H1") (pin "248") (pinfunction "VSS_248") (pintype "passive"))
      (node (ref "H1") (pin "250") (pinfunction "VSS_250") (pintype "passive"))
      (node (ref "H1") (pin "252") (pinfunction "VSS_252") (pintype "passive"))
      (node (ref "H1") (pin "254") (pinfunction "VSS_254") (pintype "passive"))
      (node (ref "H1") (pin "257") (pinfunction "VSS_257") (pintype "passive"))
      (node (ref "H1") (pin "259") (pinfunction "VSS_259") (pintype "passive"))
      (node (ref "H1") (pin "261") (pinfunction "VSS_261") (pintype "passive"))
      (node (ref "H1") (pin "263") (pinfunction "VSS_263") (pintype "passive"))
      (node (ref "H1") (pin "265") (pinfunction "VSS_265") (pintype "passive"))
      (node (ref "H1") (pin "268") (pinfunction "VSS_268") (pintype "passive"))
      (node (ref "H1") (pin "270") (pinfunction "VSS_270") (pintype "passive"))
      (node (ref "H1") (pin "272") (pinfunction "VSS_272") (pintype "passive"))
      (node (ref "H1") (pin "274") (pinfunction "VSS_274") (pintype "passive"))
      (node (ref "H1") (pin "276") (pinfunction "VSS_276") (pintype "passive"))
      (node (ref "H1") (pin "279") (pinfunction "VSS_279") (pintype "passive"))
      (node (ref "H1") (pin "281") (pinfunction "VSS_281") (pintype "passive"))
      (node (ref "H1") (pin "283") (pinfunction "VSS_283") (pintype "passive"))
      (node (ref "TP113") (pin "1") (pinfunction "1_1") (pintype "passive"))
      (node (ref "TP12") (pin "1") (pinfunction "1_1") (pintype "passive"))
      (node (ref "TP138") (pin "1") (pinfunction "1_1") (pintype "passive"))
      (node (ref "TP148") (pin "1") (pinfunction "1_1") (pintype "passive"))
      (node (ref "TP175") (pin "1") (pinfunction "1_1") (pintype "passive"))
      (node (ref "TP181") (pin "1") (pinfunction "1_1") (pintype "passive"))
      (node (ref "TP201") (pin "1") (pinfunction "1_1") (pintype "passive"))
      (node (ref "TP212") (pin "1") (pinfunction "1_1") (pintype "passive"))
      (node (ref "TP214") (pin "1") (pinfunction "1_1") (pintype "passive"))
      (node (ref "TP220") (pin "1") (pinfunction "1_1") (pintype "passive"))
      (node (ref "TP229") (pin "1") (pinfunction "1_1") (pintype "passive"))
      (node (ref "TP232") (pin "1") (pinfunction "1_1") (pintype "passive"))
      (node (ref "TP240") (pin "1") (pinfunction "1_1") (pintype "passive"))
      (node (ref "TP242") (pin "1") (pinfunction "1_1") (pintype "passive"))
      (node (ref "TP251") (pin "1") (pinfunction "1_1") (pintype "passive"))
      (node (ref "TP263") (pin "1") (pinfunction "1_1") (pintype "passive"))
      (node (ref "TP265") (pin "1") (pinfunction "1_1") (pintype "passive"))
      (node (ref "TP27") (pin "1") (pinfunction "1_1") (pintype "passive"))
      (node (ref "TP274") (pin "1") (pinfunction "1_1") (pintype "passive"))
      (node (ref "TP283") (pin "1") (pinfunction "1_1") (pintype "passive"))
      (node (ref "TP42") (pin "1") (pinfunction "1_1") (pintype "passive"))
      (node (ref "TP64") (pin "1") (pinfunction "1_1") (pintype "passive"))
      (node (ref "TP85") (pin "1") (pinfunction "1_1") (pintype "passive"))
    )
    (net (code "2") (name "Net-(H1A-A0)") (class "Default")
      (node (ref "H1") (pin "79") (pinfunction "A0_79") (pintype "input"))
      (node (ref "TP100") (pin "1") (pinfunction "1_1") (pintype "passive"))
    )
    (net (code "3") (name "Net-(H1A-A1)") (class "Default")
      (node (ref "H1") (pin "72") (pinfunction "A1_72") (pintype "input"))
      (node (ref "TP106") (pin "1") (pinfunction "1_1") (pintype "passive"))
    )
    (net (code "4") (name "Net-(H1A-A2)") (class "Default")
      (node (ref "H1") (pin "216") (pinfunction "A2_216") (pintype "input"))
      (node (ref "TP111") (pin "1") (pinfunction "1_1") (pintype "passive"))
    )
    (net (code "5") (name "Net-(H1A-A3)") (class "Default")
      (node (ref "H1") (pin "71") (pinfunction "A3_71") (pintype "input"))
      (node (ref "TP116") (pin "1") (pinfunction "1_1") (pintype "passive"))
    )
    (net (code "6") (name "Net-(H1A-A4)") (class "Default")
      (node (ref "H1") (pin "214") (pinfunction "A4_214") (pintype "input"))
      (node (ref "TP121") (pin "1") (pinfunction "1_1") (pintype "passive"))
    )
    (net (code "7") (name "Net-(H1A-A5)") (class "Default")
      (node (ref "H1") (pin "213") (pinfunction "A5_213") (pintype "input"))
      (node (ref "TP126") (pin "1") (pinfunction "1_1") (pintype "passive"))
    )
    (net (code "8") (name "Net-(H1A-A6)") (class "Default")
      (node (ref "H1") (pin "69") (pinfunction "A6_69") (pintype "input"))
      (node (ref "TP131") (pin "1") (pinfunction "1_1") (pintype "passive"))
    )
    (net (code "9") (name "Net-(H1A-A7)") (class "Default")
      (node (ref "H1") (pin "211") (pinfunction "A7_211") (pintype "input"))
      (node (ref "TP135") (pin "1") (pinfunction "1_1") (pintype "passive"))
    )
    (net (code "10") (name "Net-(H1A-A8)") (class "Default")
      (node (ref "H1") (pin "68") (pinfunction "A8_68") (pintype "input"))
      (node (ref "TP140") (pin "1") (pinfunction "1_1") (pintype "passive"))
    )
    (net (code "11") (name "Net-(H1A-A9)") (class "Default")
      (node (ref "H1") (pin "66") (pinfunction "A9_66") (pintype "input"))
      (node (ref "TP145") (pin "1") (pinfunction "1_1") (pintype "passive"))
    )
    (net (code "12") (name "Net-(H1A-A10_AP)") (class "Default")
      (node (ref "H1") (pin "225") (pinfunction "A10_AP_225") (pintype "input"))
      (node (ref "TP150") (pin "1") (pinfunction "1_1") (pintype "passive"))
    )
    (net (code "13") (name "Net-(H1A-A11)") (class "Default")
      (node (ref "H1") (pin "210") (pinfunction "A11_210") (pintype "input"))
      (node (ref "TP156") (pin "1") (pinfunction "1_1") (pintype "passive"))
    )
    (net (code "14") (name "Net-(H1A-A12)") (class "Default")
      (node (ref "H1") (pin "65") (pinfunction "A12_65") (pintype "input"))
      (node (ref "TP160") (pin "1") (pinfunction "1_1") (pintype "passive"))
    )
    (net (code "15") (name "Net-(H1A-A13)") (class "Default")
      (node (ref "H1") (pin "232") (pinfunction "A13_232") (pintype "input"))
      (node (ref "TP166") (pin "1") (pinfunction "1_1") (pintype "passive"))
    )
    (net (code "16") (name "Net-(H1A-A17{slash}NC)") (class "Default")
      (node (ref "H1") (pin "234") (pinfunction "A17/NC_234") (pintype "input"))
      (node (ref "TP190") (pin "1") (pinfunction "1_1") (pintype "passive"))
    )
    (net (code "17") (name "Net-(H1A-CAS_n{slash}A15)") (class "Default")
      (node (ref "H1") (pin "86") (pinfunction "CAS_n/A15_86") (pintype "input"))
      (node (ref "TP178") (pin "1") (pinfunction "1_1") (pintype "passive"))
    )
    (net (code "18") (name "Net-(H1A-RAS_n{slash}A16)") (class "Default")
      (node (ref "H1") (pin "82") (pinfunction "RAS_n/A16_82") (pintype "input"))
      (node (ref "TP184") (pin "1") (pinfunction "1_1") (pintype "passive"))
    )
    (net (code "19") (name "Net-(H1A-WE_n{slash}A14)") (class "Default")
      (node (ref "H1") (pin "228") (pinfunction "WE_n/A14_228") (pintype "input"))
      (node (ref "TP172") (pin "1") (pinfunction "1_1") (pintype "passive"))
    )
    (net (code "20") (name "Net-(H1B-BA0)") (class "Default")
      (node (ref "H1") (pin "81") (pinfunction "BA0_81") (pintype "input"))
      (node (ref "TP208") (pin "1") (pinfunction "1_1") (pintype "passive"))
    )
    (net (code "21") (name "Net-(H1B-BA1)") (class "Default")
      (node (ref "H1") (pin "224") (pinfunction "BA1_224") (pintype "input"))
      (node (ref "TP210") (pin "1") (pinfunction "1_1") (pintype "passive"))
    )
    (net (code "22") (name "Net-(H1C-BG0)") (class "Default")
      (node (ref "H1") (pin "63") (pinfunction "BG0_63") (pintype "input"))
      (node (ref "TP222") (pin "1") (pinfunction "1_1") (pintype "passive"))
    )
    (net (code "23") (name "Net-(H1C-BG1)") (class "Default")
      (node (ref "H1") (pin "207") (pinfunction "BG1_207") (pintype "input"))
      (node (ref "TP226") (pin "1") (pinfunction "1_1") (pintype "passive"))
    )
    (net (code "24") (name "Net-(H1D-CS0_n)") (class "Default")
      (node (ref "H1") (pin "84") (pinfunction "CS0_n_84") (pintype "input"))
      (node (ref "TP235") (pin "1") (pinfunction "1_1") (pintype "passive"))
    )
    (net (code "25") (name "Net-(H1D-CS1_n{slash}NC)") (class "Default")
      (node (ref "H1") (pin "89") (pinfunction "CS1_n/NC_89") (pintype "input"))
      (node (ref "TP237") (pin "1") (pinfunction "1_1") (pintype "passive"))
    )
    (net (code "26") (name "Net-(H1D-CS2_n{slash}C0)") (class "Default")
      (node (ref "H1") (pin "93") (pinfunction "CS2_n/C0_93") (pintype "input"))
      (node (ref "TP239") (pin "1") (pinfunction "1_1") (pintype "passive"))
    )
    (net (code "27") (name "Net-(H1D-CS3_n{slash}C1{slash}NC)") (class "Default")
      (node (ref "H1") (pin "237") (pinfunction "CS3_n/C1/NC_237") (pintype "input"))
      (node (ref "TP241") (pin "1") (pinfunction "1_1") (pintype "passive"))
    )
    (net (code "28") (name "Net-(H1E-CKE0)") (class "Default")
      (node (ref "H1") (pin "60") (pinfunction "CKE0_60") (pintype "input"))
      (node (ref "TP252") (pin "1") (pinfunction "1_1") (pintype "passive"))
    )
    (net (code "29") (name "Net-(H1E-CKE1{slash}NC)") (class "Default")
      (node (ref "H1") (pin "203") (pinfunction "CKE1/NC_203") (pintype "input"))
      (node (ref "TP255") (pin "1") (pinfunction "1_1") (pintype "passive"))
    )
    (net (code "30") (name "Net-(H1F-ODT0)") (class "Default")
      (node (ref "H1") (pin "87") (pinfunction "ODT0_87") (pintype "passive"))
      (node (ref "TP268") (pin "1") (pinfunction "1_1") (pintype "passive"))
    )
    (net (code "31") (name "Net-(H1F-ODT1{slash}NC)") (class "Default")
      (node (ref "H1") (pin "91") (pinfunction "ODT1/NC_91") (pintype "passive"))
      (node (ref "TP271") (pin "1") (pinfunction "1_1") (pintype "passive"))
    )
    (net (code "32") (name "Net-(H1G-ACT_n)") (class "Default")
      (node (ref "H1") (pin "62") (pinfunction "ACT_n_62") (pintype "input"))
      (node (ref "TP15") (pin "1") (pinfunction "1_1") (pintype "passive"))
    )
    (net (code "33") (name "Net-(H1H-DQ0)") (class "Default")
      (node (ref "H1") (pin "5") (pinfunction "DQ0_5") (pintype "bidirectional"))
      (node (ref "TP47") (pin "1") (pinfunction "1_1") (pintype "passive"))
    )
    (net (code "34") (name "Net-(H1H-DQ1)") (class "Default")
      (node (ref "H1") (pin "150") (pinfunction "DQ1_150") (pintype "bidirectional"))
      (node (ref "TP52") (pin "1") (pinfunction "1_1") (pintype "passive"))
    )
    (net (code "35") (name "Net-(H1H-DQ2)") (class "Default")
      (node (ref "H1") (pin "12") (pinfunction "DQ2_12") (pintype "bidirectional"))
      (node (ref "TP57") (pin "1") (pinfunction "1_1") (pintype "passive"))
    )
    (net (code "36") (name "Net-(H1H-DQ3)") (class "Default")
      (node (ref "H1") (pin "157") (pinfunction "DQ3_157") (pintype "bidirectional"))
      (node (ref "TP61") (pin "1") (pinfunction "1_1") (pintype "passive"))
    )
    (net (code "37") (name "Net-(H1H-DQ4)") (class "Default")
      (node (ref "H1") (pin "3") (pinfunction "DQ4_3") (pintype "bidirectional"))
      (node (ref "TP65") (pin "1") (pinfunction "1_1") (pintype "passive"))
    )
    (net (code "38") (name "Net-(H1H-DQ5)") (class "Default")
      (node (ref "H1") (pin "148") (pinfunction "DQ5_148") (pintype "bidirectional"))
      (node (ref "TP69") (pin "1") (pinfunction "1_1") (pintype "passive"))
    )
    (net (code "39") (name "Net-(H1H-DQ6)") (class "Default")
      (node (ref "H1") (pin "10") (pinfunction "DQ6_10") (pintype "bidirectional"))
      (node (ref "TP74") (pin "1") (pinfunction "1_1") (pintype "passive"))
    )
    (net (code "40") (name "Net-(H1H-DQ7)") (class "Default")
      (node (ref "H1") (pin "155") (pinfunction "DQ7_155") (pintype "bidirectional"))
      (node (ref "TP77") (pin "1") (pinfunction "1_1") (pintype "passive"))
    )
    (net (code "41") (name "Net-(H1H-DQ8)") (class "Default")
      (node (ref "H1") (pin "16") (pinfunction "DQ8_16") (pintype "bidirectional"))
      (node (ref "TP80") (pin "1") (pinfunction "1_1") (pintype "passive"))
    )
    (net (code "42") (name "Net-(H1H-DQ9)") (class "Default")
      (node (ref "H1") (pin "161") (pinfunction "DQ9_161") (pintype "bidirectional"))
      (node (ref "TP83") (pin "1") (pinfunction "1_1") (pintype "passive"))
    )
    (net (code "43") (name "Net-(H1H-DQ10)") (class "Default")
      (node (ref "H1") (pin "23") (pinfunction "DQ10_23") (pintype "bidirectional"))
      (node (ref "TP86") (pin "1") (pinfunction "1_1") (pintype "passive"))
    )
    (net (code "44") (name "Net-(H1H-DQ11)") (class "Default")
      (node (ref "H1") (pin "168") (pinfunction "DQ11_168") (pintype "bidirectional"))
      (node (ref "TP91") (pin "1") (pinfunction "1_1") (pintype "passive"))
    )
    (net (code "45") (name "Net-(H1H-DQ12)") (class "Default")
      (node (ref "H1") (pin "14") (pinfunction "DQ12_14") (pintype "bidirectional"))
      (node (ref "TP95") (pin "1") (pinfunction "1_1") (pintype "passive"))
    )
    (net (code "46") (name "Net-(H1H-DQ13)") (class "Default")
      (node (ref "H1") (pin "159") (pinfunction "DQ13_159") (pintype "bidirectional"))
      (node (ref "TP101") (pin "1") (pinfunction "1_1") (pintype "passive"))
    )
    (net (code "47") (name "Net-(H1H-DQ14)") (class "Default")
      (node (ref "H1") (pin "21") (pinfunction "DQ14_21") (pintype "bidirectional"))
      (node (ref "TP107") (pin "1") (pinfunction "1_1") (pintype "passive"))
    )
    (net (code "48") (name "Net-(H1H-DQ15)") (class "Default")
      (node (ref "H1") (pin "166") (pinfunction "DQ15_166") (pintype "bidirectional"))
      (node (ref "TP112") (pin "1") (pinfunction "1_1") (pintype "passive"))
    )
    (net (code "49") (name "Net-(H1H-DQ16)") (class "Default")
      (node (ref "H1") (pin "27") (pinfunction "DQ16_27") (pintype "bidirectional"))
      (node (ref "TP117") (pin "1") (pinfunction "1_1") (pintype "passive"))
    )
    (net (code "50") (name "Net-(H1H-DQ17)") (class "Default")
      (node (ref "H1") (pin "172") (pinfunction "DQ17_172") (pintype "bidirectional"))
      (node (ref "TP122") (pin "1") (pinfunction "1_1") (pintype "passive"))
    )
    (net (code "51") (name "Net-(H1H-DQ18)") (class "Default")
      (node (ref "H1") (pin "34") (pinfunction "DQ18_34") (pintype "bidirectional"))
      (node (ref "TP127") (pin "1") (pinfunction "1_1") (pintype "passive"))
    )
    (net (code "52") (name "Net-(H1H-DQ19)") (class "Default")
      (node (ref "H1") (pin "179") (pinfunction "DQ19_179") (pintype "bidirectional"))
      (node (ref "TP132") (pin "1") (pinfunction "1_1") (pintype "passive"))
    )
    (net (code "53") (name "Net-(H1H-DQ20)") (class "Default")
      (node (ref "H1") (pin "25") (pinfunction "DQ20_25") (pintype "bidirectional"))
      (node (ref "TP136") (pin "1") (pinfunction "1_1") (pintype "passive"))
    )
    (net (code "54") (name "Net-(H1H-DQ21)") (class "Default")
      (node (ref "H1") (pin "170") (pinfunction "DQ21_170") (pintype "bidirectional"))
      (node (ref "TP141") (pin "1") (pinfunction "1_1") (pintype "passive"))
    )
    (net (code "55") (name "Net-(H1H-DQ22)") (class "Default")
      (node (ref "H1") (pin "32") (pinfunction "DQ22_32") (pintype "bidirectional"))
      (node (ref "TP146") (pin "1") (pinfunction "1_1") (pintype "passive"))
    )
    (net (code "56") (name "Net-(H1H-DQ23)") (class "Default")
      (node (ref "H1") (pin "177") (pinfunction "DQ23_177") (pintype "bidirectional"))
      (node (ref "TP151") (pin "1") (pinfunction "1_1") (pintype "passive"))
    )
    (net (code "57") (name "Net-(H1H-DQ24)") (class "Default")
      (node (ref "H1") (pin "38") (pinfunction "DQ24_38") (pintype "bidirectional"))
      (node (ref "TP157") (pin "1") (pinfunction "1_1") (pintype "passive"))
    )
    (net (code "58") (name "Net-(H1H-DQ25)") (class "Default")
      (node (ref "H1") (pin "183") (pinfunction "DQ25_183") (pintype "bidirectional"))
      (node (ref "TP161") (pin "1") (pinfunction "1_1") (pintype "passive"))
    )
    (net (code "59") (name "Net-(H1H-DQ26)") (class "Default")
      (node (ref "H1") (pin "45") (pinfunction "DQ26_45") (pintype "bidirectional"))
      (node (ref "TP167") (pin "1") (pinfunction "1_1") (pintype "passive"))
    )
    (net (code "60") (name "Net-(H1H-DQ27)") (class "Default")
      (node (ref "H1") (pin "190") (pinfunction "DQ27_190") (pintype "bidirectional"))
      (node (ref "TP173") (pin "1") (pinfunction "1_1") (pintype "passive"))
    )
    (net (code "61") (name "Net-(H1H-DQ28)") (class "Default")
      (node (ref "H1") (pin "36") (pinfunction "DQ28_36") (pintype "bidirectional"))
      (node (ref "TP179") (pin "1") (pinfunction "1_1") (pintype "passive"))
    )
    (net (code "62") (name "Net-(H1H-DQ29)") (class "Default")
      (node (ref "H1") (pin "181") (pinfunction "DQ29_181") (pintype "bidirectional"))
      (node (ref "TP185") (pin "1") (pinfunction "1_1") (pintype "passive"))
    )
    (net (code "63") (name "Net-(H1H-DQ30)") (class "Default")
      (node (ref "H1") (pin "43") (pinfunction "DQ30_43") (pintype "bidirectional"))
      (node (ref "TP191") (pin "1") (pinfunction "1_1") (pintype "passive"))
    )
    (net (code "64") (name "Net-(H1H-DQ31)") (class "Default")
      (node (ref "H1") (pin "188") (pinfunction "DQ31_188") (pintype "bidirectional"))
      (node (ref "TP195") (pin "1") (pinfunction "1_1") (pintype "passive"))
    )
    (net (code "65") (name "Net-(H1H-DQ32)") (class "Default")
      (node (ref "H1") (pin "97") (pinfunction "DQ32_97") (pintype "bidirectional"))
      (node (ref "TP48") (pin "1") (pinfunction "1_1") (pintype "passive"))
    )
    (net (code "66") (name "Net-(H1H-DQ33)") (class "Default")
      (node (ref "H1") (pin "242") (pinfunction "DQ33_242") (pintype "bidirectional"))
      (node (ref "TP53") (pin "1") (pinfunction "1_1") (pintype "passive"))
    )
    (net (code "67") (name "Net-(H1H-DQ34)") (class "Default")
      (node (ref "H1") (pin "104") (pinfunction "DQ34_104") (pintype "bidirectional"))
      (node (ref "TP58") (pin "1") (pinfunction "1_1") (pintype "passive"))
    )
    (net (code "68") (name "Net-(H1H-DQ35)") (class "Default")
      (node (ref "H1") (pin "249") (pinfunction "DQ35_249") (pintype "bidirectional"))
      (node (ref "TP62") (pin "1") (pinfunction "1_1") (pintype "passive"))
    )
    (net (code "69") (name "Net-(H1H-DQ36)") (class "Default")
      (node (ref "H1") (pin "95") (pinfunction "DQ36_95") (pintype "bidirectional"))
      (node (ref "TP66") (pin "1") (pinfunction "1_1") (pintype "passive"))
    )
    (net (code "70") (name "Net-(H1H-DQ37)") (class "Default")
      (node (ref "H1") (pin "240") (pinfunction "DQ37_240") (pintype "bidirectional"))
      (node (ref "TP70") (pin "1") (pinfunction "1_1") (pintype "passive"))
    )
    (net (code "71") (name "Net-(H1H-DQ38)") (class "Default")
      (node (ref "H1") (pin "102") (pinfunction "DQ38_102") (pintype "bidirectional"))
      (node (ref "TP73") (pin "1") (pinfunction "1_1") (pintype "passive"))
    )
    (net (code "72") (name "Net-(H1H-DQ39)") (class "Default")
      (node (ref "H1") (pin "247") (pinfunction "DQ39_247") (pintype "bidirectional"))
      (node (ref "TP78") (pin "1") (pinfunction "1_1") (pintype "passive"))
    )
    (net (code "73") (name "Net-(H1H-DQ40)") (class "Default")
      (node (ref "H1") (pin "108") (pinfunction "DQ40_108") (pintype "bidirectional"))
      (node (ref "TP81") (pin "1") (pinfunction "1_1") (pintype "passive"))
    )
    (net (code "74") (name "Net-(H1H-DQ41)") (class "Default")
      (node (ref "H1") (pin "253") (pinfunction "DQ41_253") (pintype "bidirectional"))
      (node (ref "TP84") (pin "1") (pinfunction "1_1") (pintype "passive"))
    )
    (net (code "75") (name "Net-(H1H-DQ42)") (class "Default")
      (node (ref "H1") (pin "115") (pinfunction "DQ42_115") (pintype "bidirectional"))
      (node (ref "TP87") (pin "1") (pinfunction "1_1") (pintype "passive"))
    )
    (net (code "76") (name "Net-(H1H-DQ43)") (class "Default")
      (node (ref "H1") (pin "260") (pinfunction "DQ43_260") (pintype "bidirectional"))
      (node (ref "TP90") (pin "1") (pinfunction "1_1") (pintype "passive"))
    )
    (net (code "77") (name "Net-(H1H-DQ44)") (class "Default")
      (node (ref "H1") (pin "106") (pinfunction "DQ44_106") (pintype "bidirectional"))
      (node (ref "TP93") (pin "1") (pinfunction "1_1") (pintype "passive"))
    )
    (net (code "78") (name "Net-(H1H-DQ45)") (class "Default")
      (node (ref "H1") (pin "251") (pinfunction "DQ45_251") (pintype "bidirectional"))
      (node (ref "TP99") (pin "1") (pinfunction "1_1") (pintype "passive"))
    )
    (net (code "79") (name "Net-(H1H-DQ46)") (class "Default")
      (node (ref "H1") (pin "113") (pinfunction "DQ46_113") (pintype "bidirectional"))
      (node (ref "TP105") (pin "1") (pinfunction "1_1") (pintype "passive"))
    )
    (net (code "80") (name "Net-(H1H-DQ47)") (class "Default")
      (node (ref "H1") (pin "258") (pinfunction "DQ47_258") (pintype "bidirectional"))
      (node (ref "TP109") (pin "1") (pinfunction "1_1") (pintype "passive"))
    )
    (net (code "81") (name "Net-(H1H-DQ48)") (class "Default")
      (node (ref "H1") (pin "119") (pinfunction "DQ48_119") (pintype "bidirectional"))
      (node (ref "TP114") (pin "1") (pinfunction "1_1") (pintype "passive"))
    )
    (net (code "82") (name "Net-(H1H-DQ49)") (class "Default")
      (node (ref "H1") (pin "264") (pinfunction "DQ49_264") (pintype "bidirectional"))
      (node (ref "TP120") (pin "1") (pinfunction "1_1") (pintype "passive"))
    )
    (net (code "83") (name "Net-(H1H-DQ50)") (class "Default")
      (node (ref "H1") (pin "126") (pinfunction "DQ50_126") (pintype "bidirectional"))
      (node (ref "TP124") (pin "1") (pinfunction "1_1") (pintype "passive"))
    )
    (net (code "84") (name "Net-(H1H-DQ51)") (class "Default")
      (node (ref "H1") (pin "271") (pinfunction "DQ51_271") (pintype "bidirectional"))
      (node (ref "TP130") (pin "1") (pinfunction "1_1") (pintype "passive"))
    )
    (net (code "85") (name "Net-(H1H-DQ52)") (class "Default")
      (node (ref "H1") (pin "117") (pinfunction "DQ52_117") (pintype "bidirectional"))
      (node (ref "TP137") (pin "1") (pinfunction "1_1") (pintype "passive"))
    )
    (net (code "86") (name "Net-(H1H-DQ53)") (class "Default")
      (node (ref "H1") (pin "262") (pinfunction "DQ53_262") (pintype "bidirectional"))
      (node (ref "TP142") (pin "1") (pinfunction "1_1") (pintype "passive"))
    )
    (net (code "87") (name "Net-(H1H-DQ54)") (class "Default")
      (node (ref "H1") (pin "124") (pinfunction "DQ54_124") (pintype "bidirectional"))
      (node (ref "TP147") (pin "1") (pinfunction "1_1") (pintype "passive"))
    )
    (net (code "88") (name "Net-(H1H-DQ55)") (class "Default")
      (node (ref "H1") (pin "269") (pinfunction "DQ55_269") (pintype "bidirectional"))
      (node (ref "TP152") (pin "1") (pinfunction "1_1") (pintype "passive"))
    )
    (net (code "89") (name "Net-(H1H-DQ56)") (class "Default")
      (node (ref "H1") (pin "130") (pinfunction "DQ56_130") (pintype "bidirectional"))
      (node (ref "TP155") (pin "1") (pinfunction "1_1") (pintype "passive"))
    )
    (net (code "90") (name "Net-(H1H-DQ57)") (class "Default")
      (node (ref "H1") (pin "275") (pinfunction "DQ57_275") (pintype "bidirectional"))
      (node (ref "TP162") (pin "1") (pinfunction "1_1") (pintype "passive"))
    )
    (net (code "91") (name "Net-(H1H-DQ58)") (class "Default")
      (node (ref "H1") (pin "137") (pinfunction "DQ58_137") (pintype "bidirectional"))
      (node (ref "TP168") (pin "1") (pinfunction "1_1") (pintype "passive"))
    )
    (net (code "92") (name "Net-(H1H-DQ59)") (class "Default")
      (node (ref "H1") (pin "282") (pinfunction "DQ59_282") (pintype "bidirectional"))
      (node (ref "TP174") (pin "1") (pinfunction "1_1") (pintype "passive"))
    )
    (net (code "93") (name "Net-(H1H-DQ60)") (class "Default")
      (node (ref "H1") (pin "128") (pinfunction "DQ60_128") (pintype "bidirectional"))
      (node (ref "TP180") (pin "1") (pinfunction "1_1") (pintype "passive"))
    )
    (net (code "94") (name "Net-(H1H-DQ61)") (class "Default")
      (node (ref "H1") (pin "273") (pinfunction "DQ61_273") (pintype "bidirectional"))
      (node (ref "TP186") (pin "1") (pinfunction "1_1") (pintype "passive"))
    )
    (net (code "95") (name "Net-(H1H-DQ62)") (class "Default")
      (node (ref "H1") (pin "135") (pinfunction "DQ62_135") (pintype "bidirectional"))
      (node (ref "TP192") (pin "1") (pinfunction "1_1") (pintype "passive"))
    )
    (net (code "96") (name "Net-(H1H-DQ63)") (class "Default")
      (node (ref "H1") (pin "280") (pinfunction "DQ63_280") (pintype "bidirectional"))
      (node (ref "TP196") (pin "1") (pinfunction "1_1") (pintype "passive"))
    )
    (net (code "97") (name "Net-(H1I-CB0)") (class "Default")
      (node (ref "H1") (pin "49") (pinfunction "CB0_49") (pintype "passive"))
      (node (ref "TP213") (pin "1") (pinfunction "1_1") (pintype "passive"))
    )
    (net (code "98") (name "Net-(H1I-CB1)") (class "Default")
      (node (ref "H1") (pin "194") (pinfunction "CB1_194") (pintype "passive"))
      (node (ref "TP215") (pin "1") (pinfunction "1_1") (pintype "passive"))
    )
    (net (code "99") (name "Net-(H1I-CB2)") (class "Default")
      (node (ref "H1") (pin "56") (pinfunction "CB2_56") (pintype "passive"))
      (node (ref "TP217") (pin "1") (pinfunction "1_1") (pintype "passive"))
    )
    (net (code "100") (name "Net-(H1I-CB3)") (class "Default")
      (node (ref "H1") (pin "201") (pinfunction "CB3_201") (pintype "passive"))
      (node (ref "TP219") (pin "1") (pinfunction "1_1") (pintype "passive"))
    )
    (net (code "101") (name "Net-(H1I-CB4)") (class "Default")
      (node (ref "H1") (pin "47") (pinfunction "CB4_47") (pintype "passive"))
      (node (ref "TP221") (pin "1") (pinfunction "1_1") (pintype "passive"))
    )
    (net (code "102") (name "Net-(H1I-CB5)") (class "Default")
      (node (ref "H1") (pin "192") (pinfunction "CB5_192") (pintype "passive"))
      (node (ref "TP225") (pin "1") (pinfunction "1_1") (pintype "passive"))
    )
    (net (code "103") (name "Net-(H1I-CB6)") (class "Default")
      (node (ref "H1") (pin "54") (pinfunction "CB6_54") (pintype "passive"))
      (node (ref "TP228") (pin "1") (pinfunction "1_1") (pintype "passive"))
    )
    (net (code "104") (name "Net-(H1I-CB7)") (class "Default")
      (node (ref "H1") (pin "199") (pinfunction "CB7_199") (pintype "passive"))
      (node (ref "TP230") (pin "1") (pinfunction "1_1") (pintype "passive"))
    )
    (net (code "105") (name "Net-(H1J-DQS9_c{slash}TDQS9_c)") (class "Default")
      (node (ref "H1") (pin "8") (pinfunction "DQS9_c/TDQS9_c_8") (pintype "passive"))
      (node (ref "TP267") (pin "1") (pinfunction "1_1") (pintype "passive"))
    )
    (net (code "106") (name "Net-(H1J-DQS9_t{slash}TDQS9_t)") (class "Default")
      (node (ref "H1") (pin "7") (pinfunction "DQS9_t/TDQS9_t_7") (pintype "passive"))
      (node (ref "TP244") (pin "1") (pinfunction "1_1") (pintype "passive"))
    )
    (net (code "107") (name "Net-(H1J-DQS10_c{slash}TDQS10_c)") (class "Default")
      (node (ref "H1") (pin "19") (pinfunction "DQS10_c/TDQS10_c_19") (pintype "passive"))
      (node (ref "TP270") (pin "1") (pinfunction "1_1") (pintype "passive"))
    )
    (net (code "108") (name "Net-(H1J-DQS10_t{slash}TDQS10_t)") (class "Default")
      (node (ref "H1") (pin "18") (pinfunction "DQS10_t/TDQS10_t_18") (pintype "passive"))
      (node (ref "TP246") (pin "1") (pinfunction "1_1") (pintype "passive"))
    )
    (net (code "109") (name "Net-(H1J-DQS11_c{slash}TDQS11_c)") (class "Default")
      (node (ref "H1") (pin "30") (pinfunction "DQS11_c/TDQS11_c_30") (pintype "passive"))
      (node (ref "TP273") (pin "1") (pinfunction "1_1") (pintype "passive"))
    )
    (net (code "110") (name "Net-(H1J-DQS11_t{slash}TDQS11_t)") (class "Default")
      (node (ref "H1") (pin "29") (pinfunction "DQS11_t/TDQS11_t_29") (pintype "passive"))
      (node (ref "TP248") (pin "1") (pinfunction "1_1") (pintype "passive"))
    )
    (net (code "111") (name "Net-(H1J-DQS12_c{slash}TDQS12_c)") (class "Default")
      (node (ref "H1") (pin "41") (pinfunction "DQS12_c/TDQS12_c_41") (pintype "passive"))
      (node (ref "TP275") (pin "1") (pinfunction "1_1") (pintype "passive"))
    )
    (net (code "112") (name "Net-(H1J-DQS12_t{slash}TDQS12_t)") (class "Default")
      (node (ref "H1") (pin "40") (pinfunction "DQS12_t/TDQS12_t_40") (pintype "passive"))
      (node (ref "TP250") (pin "1") (pinfunction "1_1") (pintype "passive"))
    )
    (net (code "113") (name "Net-(H1J-DQS13_c{slash}TDQ13_c)") (class "Default")
      (node (ref "H1") (pin "100") (pinfunction "DQS13_c/TDQ13_c_100") (pintype "passive"))
      (node (ref "TP277") (pin "1") (pinfunction "1_1") (pintype "passive"))
    )
    (net (code "114") (name "Net-(H1J-DQS13_t{slash}TDQ13_t)") (class "Default")
      (node (ref "H1") (pin "99") (pinfunction "DQS13_t/TDQ13_t_99") (pintype "passive"))
      (node (ref "TP253") (pin "1") (pinfunction "1_1") (pintype "passive"))
    )
    (net (code "115") (name "Net-(H1J-DQS14_c{slash}TDQS14_c)") (class "Default")
      (node (ref "H1") (pin "111") (pinfunction "DQS14_c/TDQS14_c_111") (pintype "passive"))
      (node (ref "TP279") (pin "1") (pinfunction "1_1") (pintype "passive"))
    )
    (net (code "116") (name "Net-(H1J-DQS14_t{slash}TDQS14_t)") (class "Default")
      (node (ref "H1") (pin "110") (pinfunction "DQS14_t/TDQS14_t_110") (pintype "passive"))
      (node (ref "TP256") (pin "1") (pinfunction "1_1") (pintype "passive"))
    )
    (net (code "117") (name "Net-(H1J-DQS15_c{slash}TDQS15_c)") (class "Default")
      (node (ref "H1") (pin "122") (pinfunction "DQS15_c/TDQS15_c_122") (pintype "passive"))
      (node (ref "TP280") (pin "1") (pinfunction "1_1") (pintype "passive"))
    )
    (net (code "118") (name "Net-(H1J-DQS15_t{slash}TDQS15_t)") (class "Default")
      (node (ref "H1") (pin "121") (pinfunction "DQS15_t/TDQS15_t_121") (pintype "passive"))
      (node (ref "TP258") (pin "1") (pinfunction "1_1") (pintype "passive"))
    )
    (net (code "119") (name "Net-(H1J-DQS16_c{slash}TDQS16_c)") (class "Default")
      (node (ref "H1") (pin "133") (pinfunction "DQS16_c/TDQS16_c_133") (pintype "passive"))
      (node (ref "TP282") (pin "1") (pinfunction "1_1") (pintype "passive"))
    )
    (net (code "120") (name "Net-(H1J-DQS16_t{slash}TDQS16_t)") (class "Default")
      (node (ref "H1") (pin "132") (pinfunction "DQS16_t/TDQS16_t_132") (pintype "passive"))
      (node (ref "TP260") (pin "1") (pinfunction "1_1") (pintype "passive"))
    )
    (net (code "121") (name "Net-(H1J-DQS17_c{slash}TDQS17_c)") (class "Default")
      (node (ref "H1") (pin "52") (pinfunction "DQS17_c/TDQS17_c_52") (pintype "passive"))
      (node (ref "TP284") (pin "1") (pinfunction "1_1") (pintype "passive"))
    )
    (net (code "122") (name "Net-(H1J-DQS17_t{slash}TDQS17_t)") (class "Default")
      (node (ref "H1") (pin "51") (pinfunction "DQS17_t/TDQS17_t_51") (pintype "passive"))
      (node (ref "TP262") (pin "1") (pinfunction "1_1") (pintype "passive"))
    )
    (net (code "123") (name "Net-(H1K-CK0_c)") (class "Default")
      (node (ref "H1") (pin "75") (pinfunction "CK0_c_75") (pintype "passive"))
      (node (ref "TP22") (pin "1") (pinfunction "1_1") (pintype "passive"))
    )
    (net (code "124") (name "Net-(H1K-CK0_t)") (class "Default")
      (node (ref "H1") (pin "74") (pinfunction "CK0_t_74") (pintype "passive"))
      (node (ref "TP19") (pin "1") (pinfunction "1_1") (pintype "passive"))
    )
    (net (code "125") (name "Net-(H1K-CK1_c)") (class "Default")
      (node (ref "H1") (pin "219") (pinfunction "CK1_c_219") (pintype "passive"))
      (node (ref "TP29") (pin "1") (pinfunction "1_1") (pintype "passive"))
    )
    (net (code "126") (name "Net-(H1K-CK1_t)") (class "Default")
      (node (ref "H1") (pin "218") (pinfunction "CK1_t_218") (pintype "passive"))
      (node (ref "TP26") (pin "1") (pinfunction "1_1") (pintype "passive"))
    )
    (net (code "127") (name "Net-(H1L-PARITY)") (class "Default")
      (node (ref "H1") (pin "222") (pinfunction "PARITY_222") (pintype "passive"))
      (node (ref "TP56") (pin "1") (pinfunction "1_1") (pintype "passive"))
    )
    (net (code "128") (name "Net-(H1N-VDD-Pad59)") (class "Default")
      (node (ref "H1") (pin "59") (pinfunction "VDD_59") (pintype "passive"))
      (node (ref "TP171") (pin "1") (pinfunction "1_1") (pintype "passive"))
    )
    (net (code "129") (name "Net-(H1N-VDD-Pad61)") (class "Default")
      (node (ref "H1") (pin "61") (pinfunction "VDD_61") (pintype "passive"))
      (node (ref "TP183") (pin "1") (pinfunction "1_1") (pintype "passive"))
    )
    (net (code "130") (name "Net-(H1N-VDD-Pad64)") (class "Default")
      (node (ref "H1") (pin "64") (pinfunction "VDD_64") (pintype "passive"))
      (node (ref "TP194") (pin "1") (pinfunction "1_1") (pintype "passive"))
    )
    (net (code "131") (name "Net-(H1N-VDD-Pad67)") (class "Default")
      (node (ref "H1") (pin "67") (pinfunction "VDD_67") (pintype "passive"))
      (node (ref "TP200") (pin "1") (pinfunction "1_1") (pintype "passive"))
    )
    (net (code "132") (name "Net-(H1N-VDD-Pad70)") (class "Default")
      (node (ref "H1") (pin "70") (pinfunction "VDD_70") (pintype "passive"))
      (node (ref "TP204") (pin "1") (pinfunction "1_1") (pintype "passive"))
    )
    (net (code "133") (name "Net-(H1N-VDD-Pad73)") (class "Default")
      (node (ref "H1") (pin "73") (pinfunction "VDD_73") (pintype "passive"))
      (node (ref "TP89") (pin "1") (pinfunction "1_1") (pintype "passive"))
    )
    (net (code "134") (name "Net-(H1N-VDD-Pad76)") (class "Default")
      (node (ref "H1") (pin "76") (pinfunction "VDD_76") (pintype "passive"))
      (node (ref "TP97") (pin "1") (pinfunction "1_1") (pintype "passive"))
    )
    (net (code "135") (name "Net-(H1N-VDD-Pad80)") (class "Default")
      (node (ref "H1") (pin "80") (pinfunction "VDD_80") (pintype "passive"))
      (node (ref "TP115") (pin "1") (pinfunction "1_1") (pintype "passive"))
    )
    (net (code "136") (name "Net-(H1N-VDD-Pad83)") (class "Default")
      (node (ref "H1") (pin "83") (pinfunction "VDD_83") (pintype "passive"))
      (node (ref "TP125") (pin "1") (pinfunction "1_1") (pintype "passive"))
    )
    (net (code "137") (name "Net-(H1N-VDD-Pad85)") (class "Default")
      (node (ref "H1") (pin "85") (pinfunction "VDD_85") (pintype "passive"))
      (node (ref "TP129") (pin "1") (pinfunction "1_1") (pintype "passive"))
    )
    (net (code "138") (name "Net-(H1N-VDD-Pad88)") (class "Default")
      (node (ref "H1") (pin "88") (pinfunction "VDD_88") (pintype "passive"))
      (node (ref "TP144") (pin "1") (pinfunction "1_1") (pintype "passive"))
    )
    (net (code "139") (name "Net-(H1N-VDD-Pad90)") (class "Default")
      (node (ref "H1") (pin "90") (pinfunction "VDD_90") (pintype "passive"))
      (node (ref "TP154") (pin "1") (pinfunction "1_1") (pintype "passive"))
    )
    (net (code "140") (name "Net-(H1N-VDD-Pad92)") (class "Default")
      (node (ref "H1") (pin "92") (pinfunction "VDD_92") (pintype "passive"))
      (node (ref "TP159") (pin "1") (pinfunction "1_1") (pintype "passive"))
    )
    (net (code "141") (name "Net-(H1N-VDD-Pad204)") (class "Default")
      (node (ref "H1") (pin "204") (pinfunction "VDD_204") (pintype "passive"))
      (node (ref "TP177") (pin "1") (pinfunction "1_1") (pintype "passive"))
    )
    (net (code "142") (name "Net-(H1N-VDD-Pad206)") (class "Default")
      (node (ref "H1") (pin "206") (pinfunction "VDD_206") (pintype "passive"))
      (node (ref "TP189") (pin "1") (pinfunction "1_1") (pintype "passive"))
    )
    (net (code "143") (name "Net-(H1N-VDD-Pad209)") (class "Default")
      (node (ref "H1") (pin "209") (pinfunction "VDD_209") (pintype "passive"))
      (node (ref "TP198") (pin "1") (pinfunction "1_1") (pintype "passive"))
    )
    (net (code "144") (name "Net-(H1N-VDD-Pad212)") (class "Default")
      (node (ref "H1") (pin "212") (pinfunction "VDD_212") (pintype "passive"))
      (node (ref "TP202") (pin "1") (pinfunction "1_1") (pintype "passive"))
    )
    (net (code "145") (name "Net-(H1N-VDD-Pad215)") (class "Default")
      (node (ref "H1") (pin "215") (pinfunction "VDD_215") (pintype "passive"))
      (node (ref "TP206") (pin "1") (pinfunction "1_1") (pintype "passive"))
    )
    (net (code "146") (name "Net-(H1N-VDD-Pad217)") (class "Default")
      (node (ref "H1") (pin "217") (pinfunction "VDD_217") (pintype "passive"))
      (node (ref "TP94") (pin "1") (pinfunction "1_1") (pintype "passive"))
    )
    (net (code "147") (name "Net-(H1N-VDD-Pad220)") (class "Default")
      (node (ref "H1") (pin "220") (pinfunction "VDD_220") (pintype "passive"))
      (node (ref "TP103") (pin "1") (pinfunction "1_1") (pintype "passive"))
    )
    (net (code "148") (name "Net-(H1N-VDD-Pad223)") (class "Default")
      (node (ref "H1") (pin "223") (pinfunction "VDD_223") (pintype "passive"))
      (node (ref "TP110") (pin "1") (pinfunction "1_1") (pintype "passive"))
    )
    (net (code "149") (name "Net-(H1N-VDD-Pad226)") (class "Default")
      (node (ref "H1") (pin "226") (pinfunction "VDD_226") (pintype "passive"))
      (node (ref "TP119") (pin "1") (pinfunction "1_1") (pintype "passive"))
    )
    (net (code "150") (name "Net-(H1N-VDD-Pad229)") (class "Default")
      (node (ref "H1") (pin "229") (pinfunction "VDD_229") (pintype "passive"))
      (node (ref "TP134") (pin "1") (pinfunction "1_1") (pintype "passive"))
    )
    (net (code "151") (name "Net-(H1N-VDD-Pad231)") (class "Default")
      (node (ref "H1") (pin "231") (pinfunction "VDD_231") (pintype "passive"))
      (node (ref "TP139") (pin "1") (pinfunction "1_1") (pintype "passive"))
    )
    (net (code "152") (name "Net-(H1N-VDD-Pad233)") (class "Default")
      (node (ref "H1") (pin "233") (pinfunction "VDD_233") (pintype "passive"))
      (node (ref "TP149") (pin "1") (pinfunction "1_1") (pintype "passive"))
    )
    (net (code "153") (name "Net-(H1N-VDD-Pad236)") (class "Default")
      (node (ref "H1") (pin "236") (pinfunction "VDD_236") (pintype "passive"))
      (node (ref "TP165") (pin "1") (pinfunction "1_1") (pintype "passive"))
    )
    (net (code "154") (name "Net-(H1O-VREFCA)") (class "Default")
      (node (ref "H1") (pin "146") (pinfunction "VREFCA_146") (pintype "passive"))
      (node (ref "TP224") (pin "1") (pinfunction "1_1") (pintype "passive"))
    )
    (net (code "155") (name "Net-(H1P-VSS-Pad2)") (class "Default")
      (node (ref "H1") (pin "2") (pinfunction "VSS_2") (pintype "passive"))
      (node (ref "TP10") (pin "1") (pinfunction "1_1") (pintype "passive"))
    )
    (net (code "156") (name "Net-(H1P-VSS-Pad4)") (class "Default")
      (node (ref "H1") (pin "4") (pinfunction "VSS_4") (pintype "passive"))
      (node (ref "TP16") (pin "1") (pinfunction "1_1") (pintype "passive"))
    )
    (net (code "157") (name "Net-(H1P-VSS-Pad6)") (class "Default")
      (node (ref "H1") (pin "6") (pinfunction "VSS_6") (pintype "passive"))
      (node (ref "TP30") (pin "1") (pinfunction "1_1") (pintype "passive"))
    )
    (net (code "158") (name "Net-(H1P-VSS-Pad9)") (class "Default")
      (node (ref "H1") (pin "9") (pinfunction "VSS_9") (pintype "passive"))
      (node (ref "TP55") (pin "1") (pinfunction "1_1") (pintype "passive"))
    )
    (net (code "159") (name "Net-(H1P-VSS-Pad11)") (class "Default")
      (node (ref "H1") (pin "11") (pinfunction "VSS_11") (pintype "passive"))
      (node (ref "TP79") (pin "1") (pinfunction "1_1") (pintype "passive"))
    )
    (net (code "160") (name "Net-(H1P-VSS-Pad13)") (class "Default")
      (node (ref "H1") (pin "13") (pinfunction "VSS_13") (pintype "passive"))
      (node (ref "TP102") (pin "1") (pinfunction "1_1") (pintype "passive"))
    )
    (net (code "161") (name "Net-(H1P-VSS-Pad15)") (class "Default")
      (node (ref "H1") (pin "15") (pinfunction "VSS_15") (pintype "passive"))
      (node (ref "TP128") (pin "1") (pinfunction "1_1") (pintype "passive"))
    )
    (net (code "162") (name "Net-(H1P-VSS-Pad17)") (class "Default")
      (node (ref "H1") (pin "17") (pinfunction "VSS_17") (pintype "passive"))
      (node (ref "TP153") (pin "1") (pinfunction "1_1") (pintype "passive"))
    )
    (net (code "163") (name "Net-(H1P-VSS-Pad20)") (class "Default")
      (node (ref "H1") (pin "20") (pinfunction "VSS_20") (pintype "passive"))
      (node (ref "TP197") (pin "1") (pinfunction "1_1") (pintype "passive"))
    )
    (net (code "164") (name "Net-(H1P-VSS-Pad22)") (class "Default")
      (node (ref "H1") (pin "22") (pinfunction "VSS_22") (pintype "passive"))
      (node (ref "TP209") (pin "1") (pinfunction "1_1") (pintype "passive"))
    )
    (net (code "165") (name "Net-(H1P-VSS-Pad24)") (class "Default")
      (node (ref "H1") (pin "24") (pinfunction "VSS_24") (pintype "passive"))
      (node (ref "TP223") (pin "1") (pinfunction "1_1") (pintype "passive"))
    )
    (net (code "166") (name "Net-(H1P-VSS-Pad26)") (class "Default")
      (node (ref "H1") (pin "26") (pinfunction "VSS_26") (pintype "passive"))
      (node (ref "TP233") (pin "1") (pinfunction "1_1") (pintype "passive"))
    )
    (net (code "167") (name "Net-(H1P-VSS-Pad28)") (class "Default")
      (node (ref "H1") (pin "28") (pinfunction "VSS_28") (pintype "passive"))
      (node (ref "TP243") (pin "1") (pinfunction "1_1") (pintype "passive"))
    )
    (net (code "168") (name "Net-(H1P-VSS-Pad31)") (class "Default")
      (node (ref "H1") (pin "31") (pinfunction "VSS_31") (pintype "passive"))
      (node (ref "TP259") (pin "1") (pinfunction "1_1") (pintype "passive"))
    )
    (net (code "169") (name "Net-(H1P-VSS-Pad33)") (class "Default")
      (node (ref "H1") (pin "33") (pinfunction "VSS_33") (pintype "passive"))
      (node (ref "TP266") (pin "1") (pinfunction "1_1") (pintype "passive"))
    )
    (net (code "170") (name "Net-(H1P-VSS-Pad35)") (class "Default")
      (node (ref "H1") (pin "35") (pinfunction "VSS_35") (pintype "passive"))
      (node (ref "TP276") (pin "1") (pinfunction "1_1") (pintype "passive"))
    )
    (net (code "171") (name "Net-(H1P-VSS-Pad37)") (class "Default")
      (node (ref "H1") (pin "37") (pinfunction "VSS_37") (pintype "passive"))
      (node (ref "TP8") (pin "1") (pinfunction "1_1") (pintype "passive"))
    )
    (net (code "172") (name "Net-(H1P-VSS-Pad39)") (class "Default")
      (node (ref "H1") (pin "39") (pinfunction "VSS_39") (pintype "passive"))
      (node (ref "TP13") (pin "1") (pinfunction "1_1") (pintype "passive"))
    )
    (net (code "173") (name "Net-(H1P-VSS-Pad42)") (class "Default")
      (node (ref "H1") (pin "42") (pinfunction "VSS_42") (pintype "passive"))
      (node (ref "TP32") (pin "1") (pinfunction "1_1") (pintype "passive"))
    )
    (net (code "174") (name "Net-(H1P-VSS-Pad44)") (class "Default")
      (node (ref "H1") (pin "44") (pinfunction "VSS_44") (pintype "passive"))
      (node (ref "TP45") (pin "1") (pinfunction "1_1") (pintype "passive"))
    )
    (net (code "175") (name "Net-(H1P-VSS-Pad46)") (class "Default")
      (node (ref "H1") (pin "46") (pinfunction "VSS_46") (pintype "passive"))
      (node (ref "TP68") (pin "1") (pinfunction "1_1") (pintype "passive"))
    )
    (net (code "176") (name "Net-(H1P-VSS-Pad48)") (class "Default")
      (node (ref "H1") (pin "48") (pinfunction "VSS_48") (pintype "passive"))
      (node (ref "TP88") (pin "1") (pinfunction "1_1") (pintype "passive"))
    )
    (net (code "177") (name "Net-(H1P-VSS-Pad50)") (class "Default")
      (node (ref "H1") (pin "50") (pinfunction "VSS_50") (pintype "passive"))
      (node (ref "TP118") (pin "1") (pinfunction "1_1") (pintype "passive"))
    )
    (net (code "178") (name "Net-(H1P-VSS-Pad53)") (class "Default")
      (node (ref "H1") (pin "53") (pinfunction "VSS_53") (pintype "passive"))
      (node (ref "TP158") (pin "1") (pinfunction "1_1") (pintype "passive"))
    )
    (net (code "179") (name "Net-(H1P-VSS-Pad55)") (class "Default")
      (node (ref "H1") (pin "55") (pinfunction "VSS_55") (pintype "passive"))
      (node (ref "TP187") (pin "1") (pinfunction "1_1") (pintype "passive"))
    )
    (net (code "180") (name "Net-(H1P-VSS-Pad57)") (class "Default")
      (node (ref "H1") (pin "57") (pinfunction "VSS_57") (pintype "passive"))
      (node (ref "TP203") (pin "1") (pinfunction "1_1") (pintype "passive"))
    )
    (net (code "181") (name "Net-(H1P-VSS-Pad94)") (class "Default")
      (node (ref "H1") (pin "94") (pinfunction "VSS_94") (pintype "passive"))
      (node (ref "TP211") (pin "1") (pinfunction "1_1") (pintype "passive"))
    )
    (net (code "182") (name "Net-(H1P-VSS-Pad96)") (class "Default")
      (node (ref "H1") (pin "96") (pinfunction "VSS_96") (pintype "passive"))
      (node (ref "TP227") (pin "1") (pinfunction "1_1") (pintype "passive"))
    )
    (net (code "183") (name "Net-(H1P-VSS-Pad98)") (class "Default")
      (node (ref "H1") (pin "98") (pinfunction "VSS_98") (pintype "passive"))
      (node (ref "TP234") (pin "1") (pinfunction "1_1") (pintype "passive"))
    )
    (net (code "184") (name "Net-(H1P-VSS-Pad101)") (class "Default")
      (node (ref "H1") (pin "101") (pinfunction "VSS_101") (pintype "passive"))
      (node (ref "TP247") (pin "1") (pinfunction "1_1") (pintype "passive"))
    )
    (net (code "185") (name "Net-(H1P-VSS-Pad103)") (class "Default")
      (node (ref "H1") (pin "103") (pinfunction "VSS_103") (pintype "passive"))
      (node (ref "TP261") (pin "1") (pinfunction "1_1") (pintype "passive"))
    )
    (net (code "186") (name "Net-(H1P-VSS-Pad105)") (class "Default")
      (node (ref "H1") (pin "105") (pinfunction "VSS_105") (pintype "passive"))
      (node (ref "TP269") (pin "1") (pinfunction "1_1") (pintype "passive"))
    )
    (net (code "187") (name "Net-(H1P-VSS-Pad107)") (class "Default")
      (node (ref "H1") (pin "107") (pinfunction "VSS_107") (pintype "passive"))
      (node (ref "TP278") (pin "1") (pinfunction "1_1") (pintype "passive"))
    )
    (net (code "188") (name "Net-(H1P-VSS-Pad109)") (class "Default")
      (node (ref "H1") (pin "109") (pinfunction "VSS_109") (pintype "passive"))
      (node (ref "TP9") (pin "1") (pinfunction "1_1") (pintype "passive"))
    )
    (net (code "189") (name "Net-(H1P-VSS-Pad112)") (class "Default")
      (node (ref "H1") (pin "112") (pinfunction "VSS_112") (pintype "passive"))
      (node (ref "TP18") (pin "1") (pinfunction "1_1") (pintype "passive"))
    )
    (net (code "190") (name "Net-(H1P-VSS-Pad114)") (class "Default")
      (node (ref "H1") (pin "114") (pinfunction "VSS_114") (pintype "passive"))
      (node (ref "TP34") (pin "1") (pinfunction "1_1") (pintype "passive"))
    )
    (net (code "191") (name "Net-(H1P-VSS-Pad116)") (class "Default")
      (node (ref "H1") (pin "116") (pinfunction "VSS_116") (pintype "passive"))
      (node (ref "TP50") (pin "1") (pinfunction "1_1") (pintype "passive"))
    )
    (net (code "192") (name "Net-(H1P-VSS-Pad118)") (class "Default")
      (node (ref "H1") (pin "118") (pinfunction "VSS_118") (pintype "passive"))
      (node (ref "TP72") (pin "1") (pinfunction "1_1") (pintype "passive"))
    )
    (net (code "193") (name "Net-(H1P-VSS-Pad120)") (class "Default")
      (node (ref "H1") (pin "120") (pinfunction "VSS_120") (pintype "passive"))
      (node (ref "TP92") (pin "1") (pinfunction "1_1") (pintype "passive"))
    )
    (net (code "194") (name "Net-(H1P-VSS-Pad123)") (class "Default")
      (node (ref "H1") (pin "123") (pinfunction "VSS_123") (pintype "passive"))
      (node (ref "TP133") (pin "1") (pinfunction "1_1") (pintype "passive"))
    )
    (net (code "195") (name "Net-(H1P-VSS-Pad125)") (class "Default")
      (node (ref "H1") (pin "125") (pinfunction "VSS_125") (pintype "passive"))
      (node (ref "TP163") (pin "1") (pinfunction "1_1") (pintype "passive"))
    )
    (net (code "196") (name "Net-(H1P-VSS-Pad127)") (class "Default")
      (node (ref "H1") (pin "127") (pinfunction "VSS_127") (pintype "passive"))
      (node (ref "TP193") (pin "1") (pinfunction "1_1") (pintype "passive"))
    )
    (net (code "197") (name "Net-(H1P-VSS-Pad129)") (class "Default")
      (node (ref "H1") (pin "129") (pinfunction "VSS_129") (pintype "passive"))
      (node (ref "TP205") (pin "1") (pinfunction "1_1") (pintype "passive"))
    )
    (net (code "198") (name "Net-(H1P-VSS-Pad131)") (class "Default")
      (node (ref "H1") (pin "131") (pinfunction "VSS_131") (pintype "passive"))
      (node (ref "TP216") (pin "1") (pinfunction "1_1") (pintype "passive"))
    )
    (net (code "199") (name "Net-(H1P-VSS-Pad134)") (class "Default")
      (node (ref "H1") (pin "134") (pinfunction "VSS_134") (pintype "passive"))
      (node (ref "TP236") (pin "1") (pinfunction "1_1") (pintype "passive"))
    )
    (net (code "200") (name "Net-(H1P-VSS-Pad136)") (class "Default")
      (node (ref "H1") (pin "136") (pinfunction "VSS_136") (pintype "passive"))
      (node (ref "TP245") (pin "1") (pinfunction "1_1") (pintype "passive"))
    )
    (net (code "201") (name "Net-(H1P-VSS-Pad138)") (class "Default")
      (node (ref "H1") (pin "138") (pinfunction "VSS_138") (pintype "passive"))
      (node (ref "TP254") (pin "1") (pinfunction "1_1") (pintype "passive"))
    )
    (net (code "202") (name "Net-(H1P-VSS-Pad147)") (class "Default")
      (node (ref "H1") (pin "147") (pinfunction "VSS_147") (pintype "passive"))
      (node (ref "TP14") (pin "1") (pinfunction "1_1") (pintype "passive"))
    )
    (net (code "203") (name "Net-(H1P-VSS-Pad149)") (class "Default")
      (node (ref "H1") (pin "149") (pinfunction "VSS_149") (pintype "passive"))
      (node (ref "TP24") (pin "1") (pinfunction "1_1") (pintype "passive"))
    )
    (net (code "204") (name "Net-(H1P-VSS-Pad151)") (class "Default")
      (node (ref "H1") (pin "151") (pinfunction "VSS_151") (pintype "passive"))
      (node (ref "TP36") (pin "1") (pinfunction "1_1") (pintype "passive"))
    )
    (net (code "205") (name "Net-(H1P-VSS-Pad154)") (class "Default")
      (node (ref "H1") (pin "154") (pinfunction "VSS_154") (pintype "passive"))
      (node (ref "TP76") (pin "1") (pinfunction "1_1") (pintype "passive"))
    )
    (net (code "206") (name "Net-(H1P-VSS-Pad156)") (class "Default")
      (node (ref "H1") (pin "156") (pinfunction "VSS_156") (pintype "passive"))
      (node (ref "TP96") (pin "1") (pinfunction "1_1") (pintype "passive"))
    )
    (net (code "207") (name "Net-(H1P-VSS-Pad158)") (class "Default")
      (node (ref "H1") (pin "158") (pinfunction "VSS_158") (pintype "passive"))
      (node (ref "TP123") (pin "1") (pinfunction "1_1") (pintype "passive"))
    )
    (net (code "208") (name "Net-(H1P-VSS-Pad160)") (class "Default")
      (node (ref "H1") (pin "160") (pinfunction "VSS_160") (pintype "passive"))
      (node (ref "TP143") (pin "1") (pinfunction "1_1") (pintype "passive"))
    )
    (net (code "209") (name "Net-(H1P-VSS-Pad162)") (class "Default")
      (node (ref "H1") (pin "162") (pinfunction "VSS_162") (pintype "passive"))
      (node (ref "TP169") (pin "1") (pinfunction "1_1") (pintype "passive"))
    )
    (net (code "210") (name "Net-(H1P-VSS-Pad165)") (class "Default")
      (node (ref "H1") (pin "165") (pinfunction "VSS_165") (pintype "passive"))
      (node (ref "TP207") (pin "1") (pinfunction "1_1") (pintype "passive"))
    )
    (net (code "211") (name "Net-(H1P-VSS-Pad167)") (class "Default")
      (node (ref "H1") (pin "167") (pinfunction "VSS_167") (pintype "passive"))
      (node (ref "TP218") (pin "1") (pinfunction "1_1") (pintype "passive"))
    )
    (net (code "212") (name "Net-(H1P-VSS-Pad169)") (class "Default")
      (node (ref "H1") (pin "169") (pinfunction "VSS_169") (pintype "passive"))
      (node (ref "TP231") (pin "1") (pinfunction "1_1") (pintype "passive"))
    )
    (net (code "213") (name "Net-(H1P-VSS-Pad171)") (class "Default")
      (node (ref "H1") (pin "171") (pinfunction "VSS_171") (pintype "passive"))
      (node (ref "TP238") (pin "1") (pinfunction "1_1") (pintype "passive"))
    )
    (net (code "214") (name "Net-(H1P-VSS-Pad173)") (class "Default")
      (node (ref "H1") (pin "173") (pinfunction "VSS_173") (pintype "passive"))
      (node (ref "TP249") (pin "1") (pinfunction "1_1") (pintype "passive"))
    )
    (net (code "215") (name "Net-(H1P-VSS-Pad176)") (class "Default")
      (node (ref "H1") (pin "176") (pinfunction "VSS_176") (pintype "passive"))
      (node (ref "TP264") (pin "1") (pinfunction "1_1") (pintype "passive"))
    )
    (net (code "216") (name "Net-(H1P-VSS-Pad178)") (class "Default")
      (node (ref "H1") (pin "178") (pinfunction "VSS_178") (pintype "passive"))
      (node (ref "TP272") (pin "1") (pinfunction "1_1") (pintype "passive"))
    )
    (net (code "217") (name "Net-(H1P-VSS-Pad180)") (class "Default")
      (node (ref "H1") (pin "180") (pinfunction "VSS_180") (pintype "passive"))
      (node (ref "TP281") (pin "1") (pinfunction "1_1") (pintype "passive"))
    )
    (net (code "218") (name "Net-(H1P-VSS-Pad182)") (class "Default")
      (node (ref "H1") (pin "182") (pinfunction "VSS_182") (pintype "passive"))
      (node (ref "TP11") (pin "1") (pinfunction "1_1") (pintype "passive"))
    )
    (net (code "219") (name "Net-(H1P-VSS-Pad184)") (class "Default")
      (node (ref "H1") (pin "184") (pinfunction "VSS_184") (pintype "passive"))
      (node (ref "TP21") (pin "1") (pinfunction "1_1") (pintype "passive"))
    )
    (net (code "220") (name "Net-(H1P-VSS-Pad187)") (class "Default")
      (node (ref "H1") (pin "187") (pinfunction "VSS_187") (pintype "passive"))
      (node (ref "TP39") (pin "1") (pinfunction "1_1") (pintype "passive"))
    )
    (net (code "221") (name "Net-(H1P-VSS-Pad189)") (class "Default")
      (node (ref "H1") (pin "189") (pinfunction "VSS_189") (pintype "passive"))
      (node (ref "TP60") (pin "1") (pinfunction "1_1") (pintype "passive"))
    )
    (net (code "222") (name "Net-(H1P-VSS-Pad191)") (class "Default")
      (node (ref "H1") (pin "191") (pinfunction "VSS_191") (pintype "passive"))
      (node (ref "TP82") (pin "1") (pinfunction "1_1") (pintype "passive"))
    )
    (net (code "223") (name "Net-(H1P-VSS-Pad193)") (class "Default")
      (node (ref "H1") (pin "193") (pinfunction "VSS_193") (pintype "passive"))
      (node (ref "TP108") (pin "1") (pinfunction "1_1") (pintype "passive"))
    )
    (net (code "224") (name "Net-(H1P-VSS-Pad200)") (class "Default")
      (node (ref "H1") (pin "200") (pinfunction "VSS_200") (pintype "passive"))
      (node (ref "TP199") (pin "1") (pinfunction "1_1") (pintype "passive"))
    )
    (net (code "225") (name "Net-(H1P-VSS-Pad246)") (class "Default")
      (node (ref "H1") (pin "246") (pinfunction "VSS_246") (pintype "passive"))
      (node (ref "TP257") (pin "1") (pinfunction "1_1") (pintype "passive"))
    )
    (net (code "226") (name "Net-(H1R-VPP-Pad142)") (class "Default")
      (node (ref "H1") (pin "142") (pinfunction "VPP_142") (pintype "passive"))
      (node (ref "TP37") (pin "1") (pinfunction "1_1") (pintype "passive"))
    )
    (net (code "227") (name "Net-(H1R-VPP-Pad143)") (class "Default")
      (node (ref "H1") (pin "143") (pinfunction "VPP_143") (pintype "passive"))
      (node (ref "TP43") (pin "1") (pinfunction "1_1") (pintype "passive"))
    )
    (net (code "228") (name "Net-(H1R-VPP-Pad286)") (class "Default")
      (node (ref "H1") (pin "286") (pinfunction "VPP_286") (pintype "passive"))
      (node (ref "TP40") (pin "1") (pinfunction "1_1") (pintype "passive"))
    )
    (net (code "229") (name "Net-(H1R-VPP-Pad287)") (class "Default")
      (node (ref "H1") (pin "287") (pinfunction "VPP_287") (pintype "passive"))
      (node (ref "TP46") (pin "1") (pinfunction "1_1") (pintype "passive"))
    )
    (net (code "230") (name "Net-(H1R-VPP-Pad288)") (class "Default")
      (node (ref "H1") (pin "288") (pinfunction "VPP_288") (pintype "passive"))
      (node (ref "TP51") (pin "1") (pinfunction "1_1") (pintype "passive"))
    )
    (net (code "231") (name "Net-(H1S-VTT-Pad77)") (class "Default")
      (node (ref "H1") (pin "77") (pinfunction "VTT_77") (pintype "passive"))
      (node (ref "TP98") (pin "1") (pinfunction "1_1") (pintype "passive"))
    )
    (net (code "232") (name "Net-(H1S-VTT-Pad221)") (class "Default")
      (node (ref "H1") (pin "221") (pinfunction "VTT_221") (pintype "passive"))
      (node (ref "TP104") (pin "1") (pinfunction "1_1") (pintype "passive"))
    )
    (net (code "233") (name "Net-(H1T-ALERT_n)") (class "Default")
      (node (ref "H1") (pin "208") (pinfunction "ALERT_n_208") (pintype "passive"))
      (node (ref "TP164") (pin "1") (pinfunction "1_1") (pintype "passive"))
    )
    (net (code "234") (name "Net-(H1T-RESET_n)") (class "Default")
      (node (ref "H1") (pin "58") (pinfunction "RESET_n_58") (pintype "passive"))
      (node (ref "TP170") (pin "1") (pinfunction "1_1") (pintype "passive"))
    )
    (net (code "235") (name "Net-(H1T-RFU-Pad144)") (class "Default")
      (node (ref "H1") (pin "144") (pinfunction "RFU_144") (pintype "passive"))
      (node (ref "TP188") (pin "1") (pinfunction "1_1") (pintype "passive"))
    )
    (net (code "236") (name "Net-(H1T-RFU-Pad205)") (class "Default")
      (node (ref "H1") (pin "205") (pinfunction "RFU_205") (pintype "passive"))
      (node (ref "TP176") (pin "1") (pinfunction "1_1") (pintype "passive"))
    )
    (net (code "237") (name "Net-(H1T-RFU-Pad227)") (class "Default")
      (node (ref "H1") (pin "227") (pinfunction "RFU_227") (pintype "passive"))
      (node (ref "TP182") (pin "1") (pinfunction "1_1") (pintype "passive"))
    )
    (net (code "238") (name "Net-(H1U-DQS0_c)") (class "Default")
      (node (ref "H1") (pin "152") (pinfunction "DQS0_c_152") (pintype "bidirectional"))
      (node (ref "TP17") (pin "1") (pinfunction "1_1") (pintype "passive"))
    )
    (net (code "239") (name "Net-(H1U-DQS0_t)") (class "Default")
      (node (ref "H1") (pin "153") (pinfunction "DQS0_t_153") (pintype "bidirectional"))
      (node (ref "TP20") (pin "1") (pinfunction "1_1") (pintype "passive"))
    )
    (net (code "240") (name "Net-(H1U-DQS1_c)") (class "Default")
      (node (ref "H1") (pin "163") (pinfunction "DQS1_c_163") (pintype "bidirectional"))
      (node (ref "TP23") (pin "1") (pinfunction "1_1") (pintype "passive"))
    )
    (net (code "241") (name "Net-(H1U-DQS1_t)") (class "Default")
      (node (ref "H1") (pin "164") (pinfunction "DQS1_t_164") (pintype "bidirectional"))
      (node (ref "TP25") (pin "1") (pinfunction "1_1") (pintype "passive"))
    )
    (net (code "242") (name "Net-(H1U-DQS2_c)") (class "Default")
      (node (ref "H1") (pin "174") (pinfunction "DQS2_c_174") (pintype "bidirectional"))
      (node (ref "TP28") (pin "1") (pinfunction "1_1") (pintype "passive"))
    )
    (net (code "243") (name "Net-(H1U-DQS2_t)") (class "Default")
      (node (ref "H1") (pin "175") (pinfunction "DQS2_t_175") (pintype "bidirectional"))
      (node (ref "TP31") (pin "1") (pinfunction "1_1") (pintype "passive"))
    )
    (net (code "244") (name "Net-(H1U-DQS3_c)") (class "Default")
      (node (ref "H1") (pin "185") (pinfunction "DQS3_c_185") (pintype "bidirectional"))
      (node (ref "TP33") (pin "1") (pinfunction "1_1") (pintype "passive"))
    )
    (net (code "245") (name "Net-(H1U-DQS3_t)") (class "Default")
      (node (ref "H1") (pin "186") (pinfunction "DQS3_t_186") (pintype "bidirectional"))
      (node (ref "TP35") (pin "1") (pinfunction "1_1") (pintype "passive"))
    )
    (net (code "246") (name "Net-(H1U-DQS4_c)") (class "Default")
      (node (ref "H1") (pin "244") (pinfunction "DQS4_c_244") (pintype "bidirectional"))
      (node (ref "TP38") (pin "1") (pinfunction "1_1") (pintype "passive"))
    )
    (net (code "247") (name "Net-(H1U-DQS4_t)") (class "Default")
      (node (ref "H1") (pin "245") (pinfunction "DQS4_t_245") (pintype "bidirectional"))
      (node (ref "TP41") (pin "1") (pinfunction "1_1") (pintype "passive"))
    )
    (net (code "248") (name "Net-(H1U-DQS5_c)") (class "Default")
      (node (ref "H1") (pin "255") (pinfunction "DQS5_c_255") (pintype "bidirectional"))
      (node (ref "TP44") (pin "1") (pinfunction "1_1") (pintype "passive"))
    )
    (net (code "249") (name "Net-(H1U-DQS5_t)") (class "Default")
      (node (ref "H1") (pin "256") (pinfunction "DQS5_t_256") (pintype "bidirectional"))
      (node (ref "TP49") (pin "1") (pinfunction "1_1") (pintype "passive"))
    )
    (net (code "250") (name "Net-(H1U-DQS6_c)") (class "Default")
      (node (ref "H1") (pin "266") (pinfunction "DQS6_c_266") (pintype "bidirectional"))
      (node (ref "TP54") (pin "1") (pinfunction "1_1") (pintype "passive"))
    )
    (net (code "251") (name "Net-(H1U-DQS6_t)") (class "Default")
      (node (ref "H1") (pin "267") (pinfunction "DQS6_t_267") (pintype "bidirectional"))
      (node (ref "TP59") (pin "1") (pinfunction "1_1") (pintype "passive"))
    )
    (net (code "252") (name "Net-(H1U-DQS7_c)") (class "Default")
      (node (ref "H1") (pin "277") (pinfunction "DQS7_c_277") (pintype "bidirectional"))
      (node (ref "TP63") (pin "1") (pinfunction "1_1") (pintype "passive"))
    )
    (net (code "253") (name "Net-(H1U-DQS7_t)") (class "Default")
      (node (ref "H1") (pin "278") (pinfunction "DQS7_t_278") (pintype "bidirectional"))
      (node (ref "TP67") (pin "1") (pinfunction "1_1") (pintype "passive"))
    )
    (net (code "254") (name "Net-(H1U-DQS8_c)") (class "Default")
      (node (ref "H1") (pin "196") (pinfunction "DQS8_c_196") (pintype "bidirectional"))
      (node (ref "TP71") (pin "1") (pinfunction "1_1") (pintype "passive"))
    )
    (net (code "255") (name "Net-(H1U-DQS8_t)") (class "Default")
      (node (ref "H1") (pin "197") (pinfunction "DQS8_t_197") (pintype "bidirectional"))
      (node (ref "TP75") (pin "1") (pinfunction "1_1") (pintype "passive"))
    )
  )
)
